# V2_2.net
KiCad netlist of a schematic drawn in EAGLE
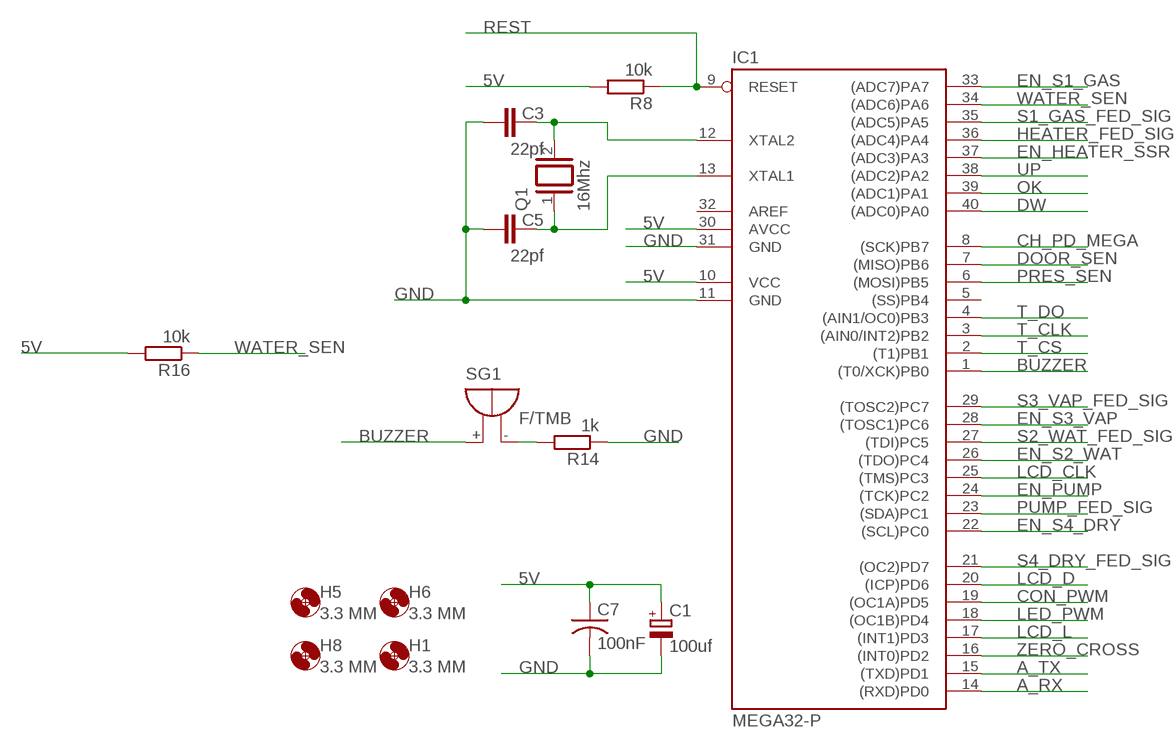
[diagram p0: schematic, sheet 1]
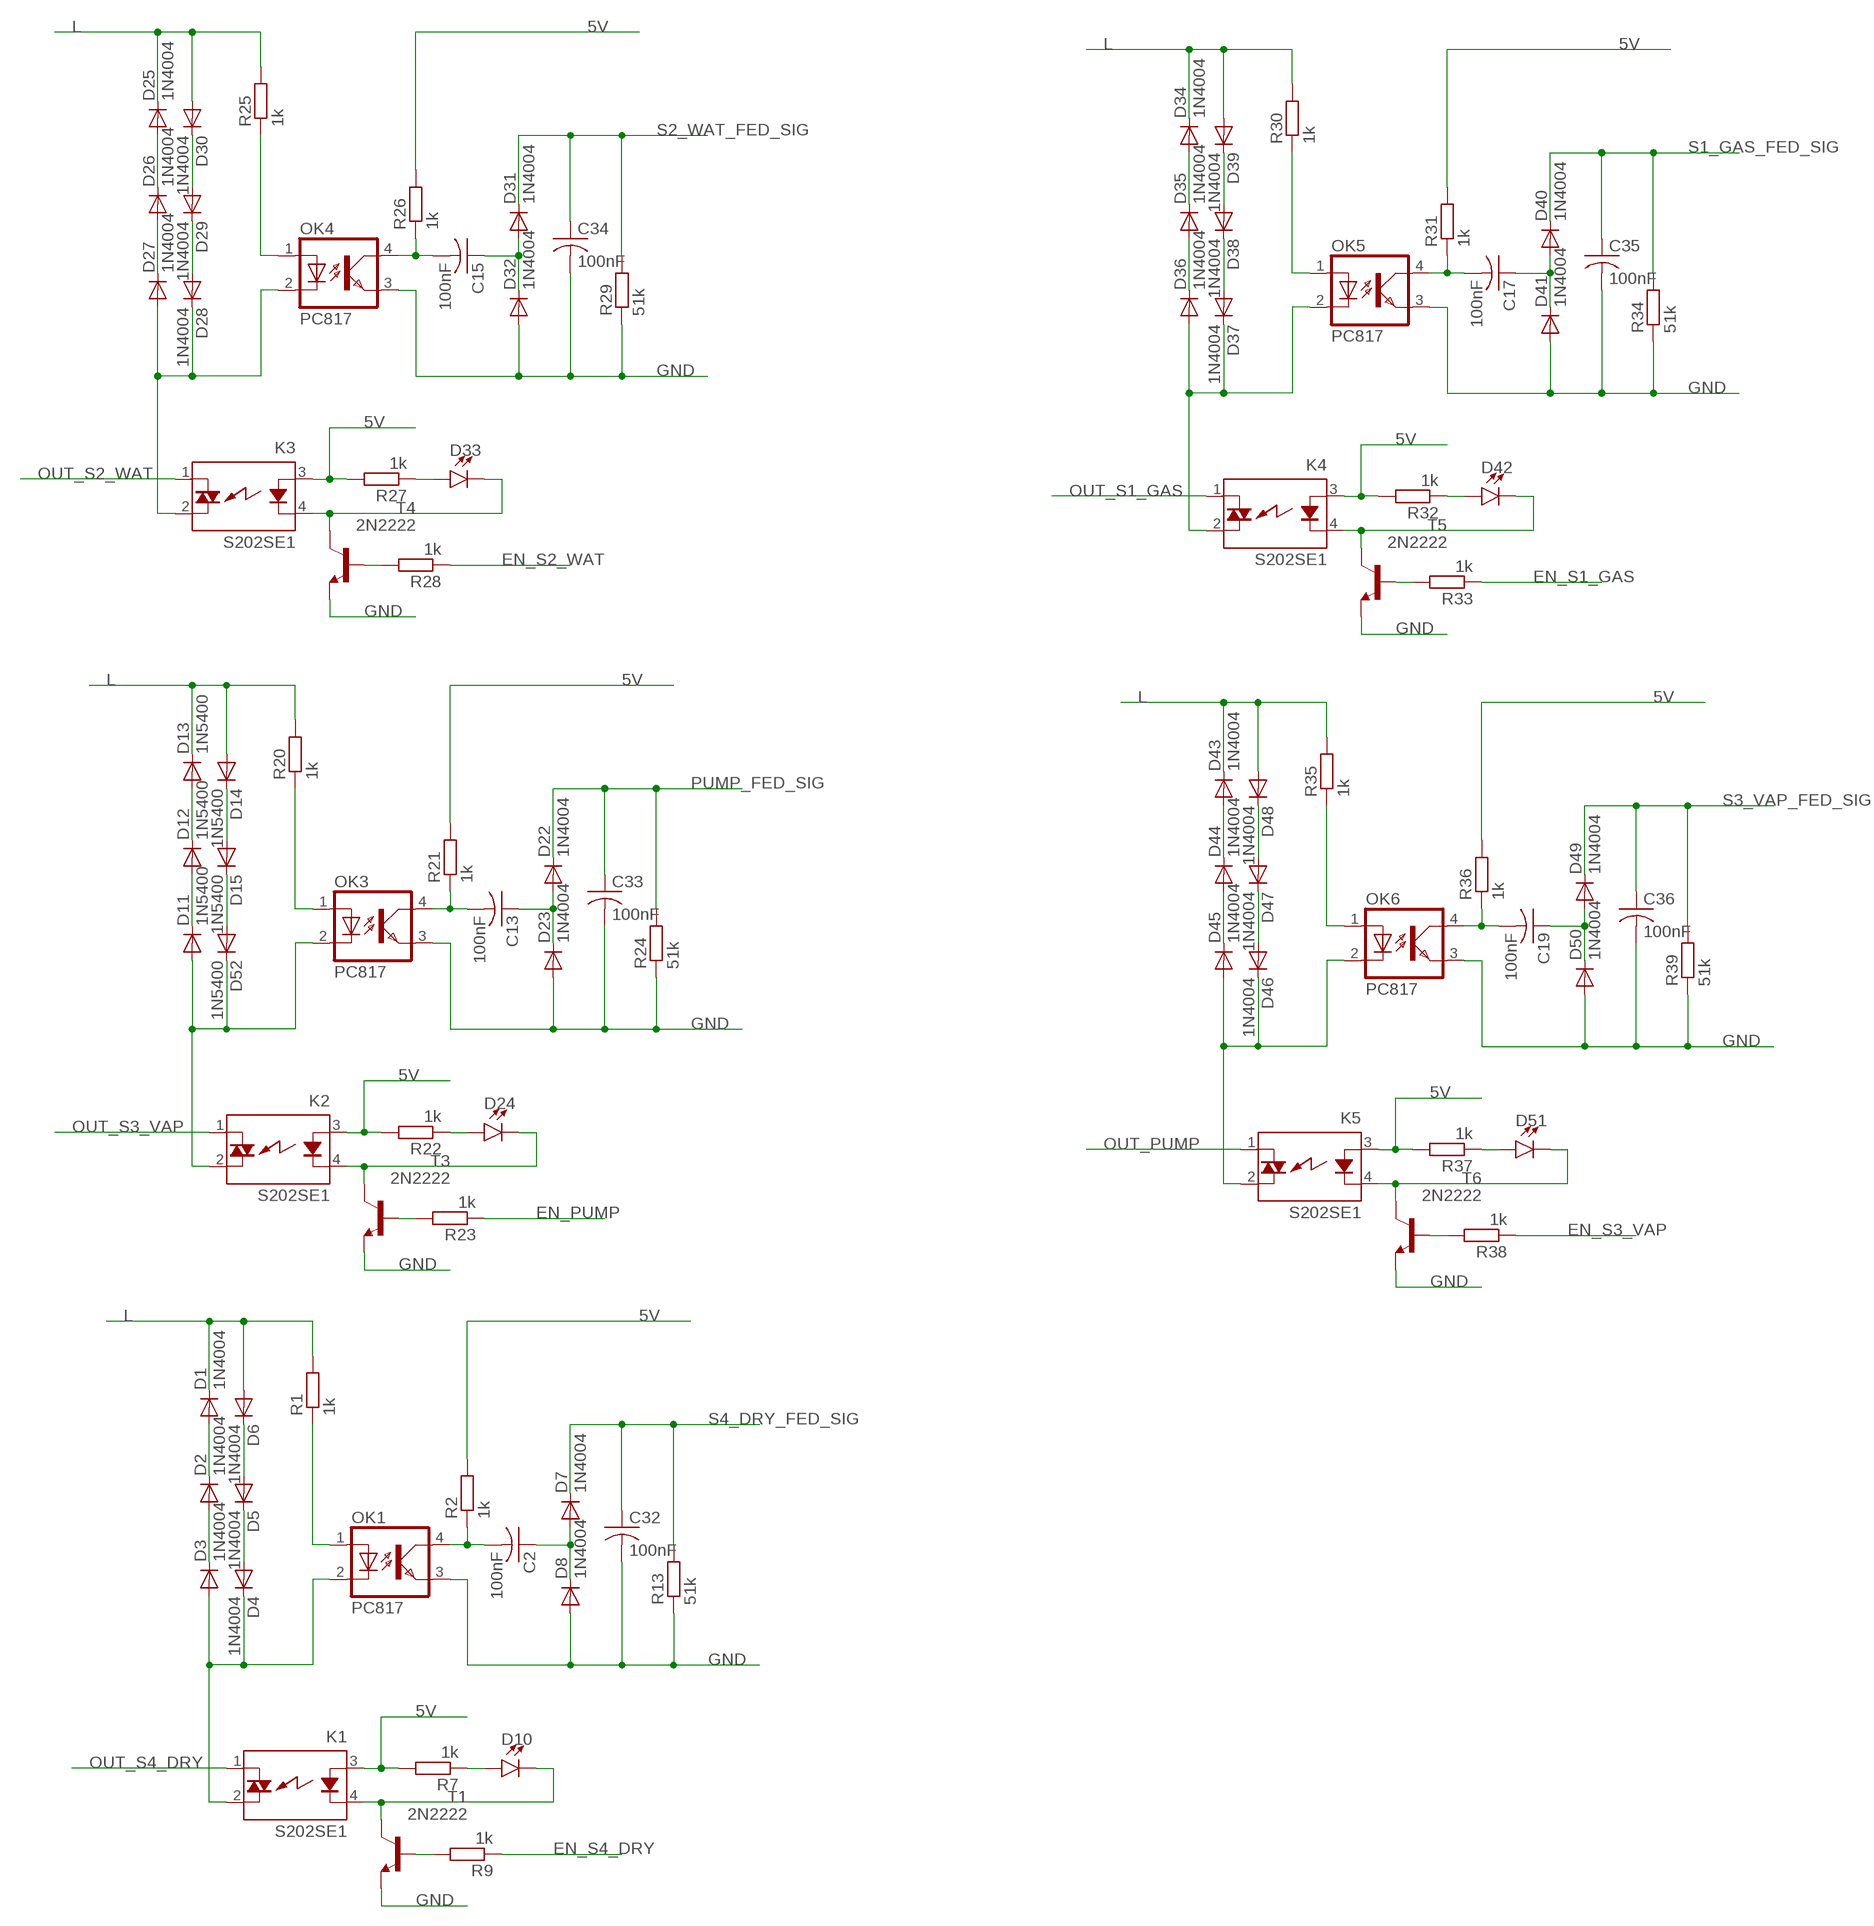
[diagram p1: schematic, sheet 2]
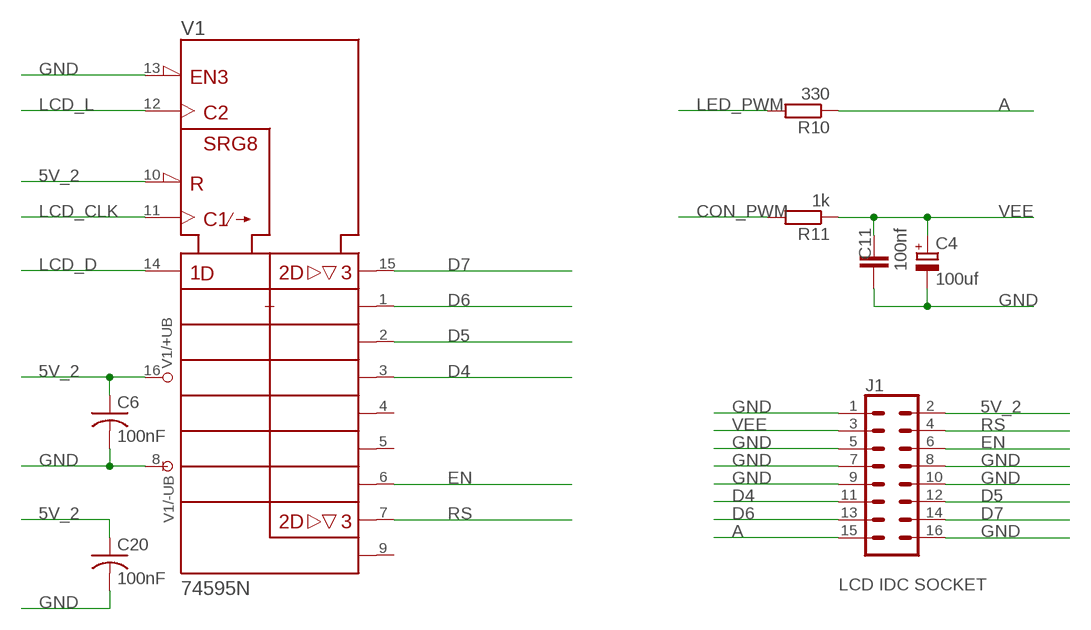
[diagram p2: schematic, sheet 3]
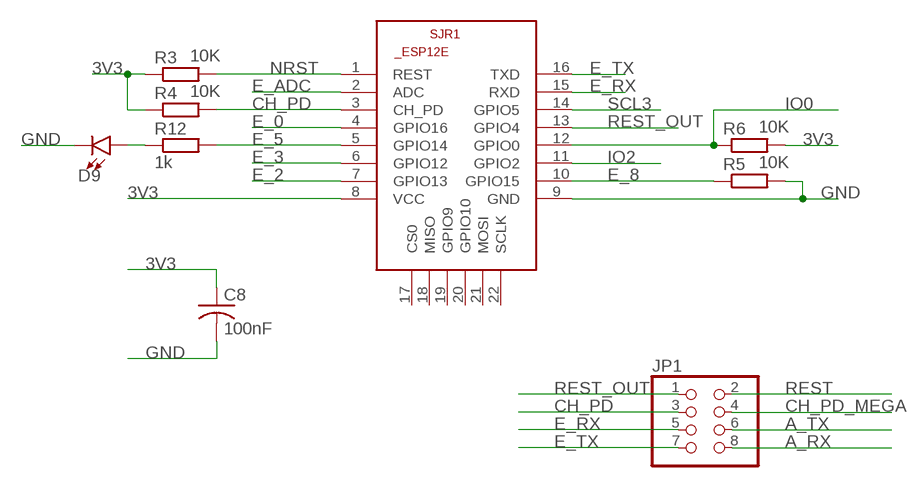
[diagram p3: schematic, sheet 4]
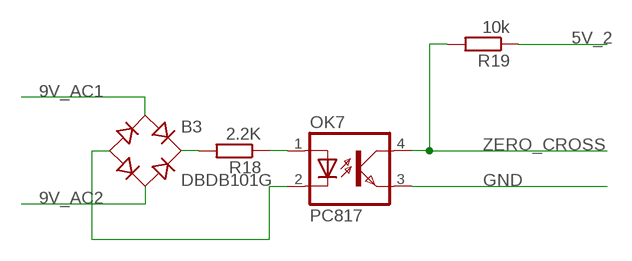
[diagram p4: schematic, sheet 5]
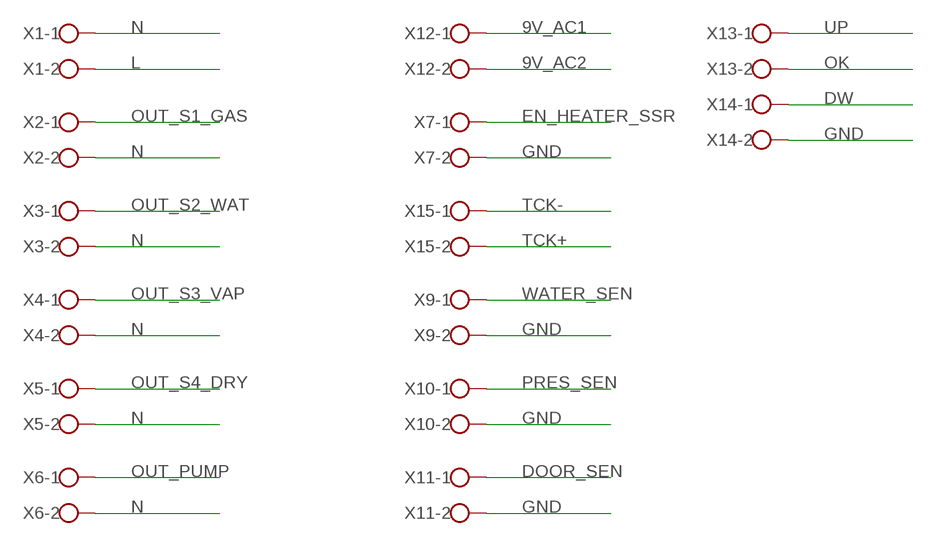
[diagram p5: schematic, sheet 6]
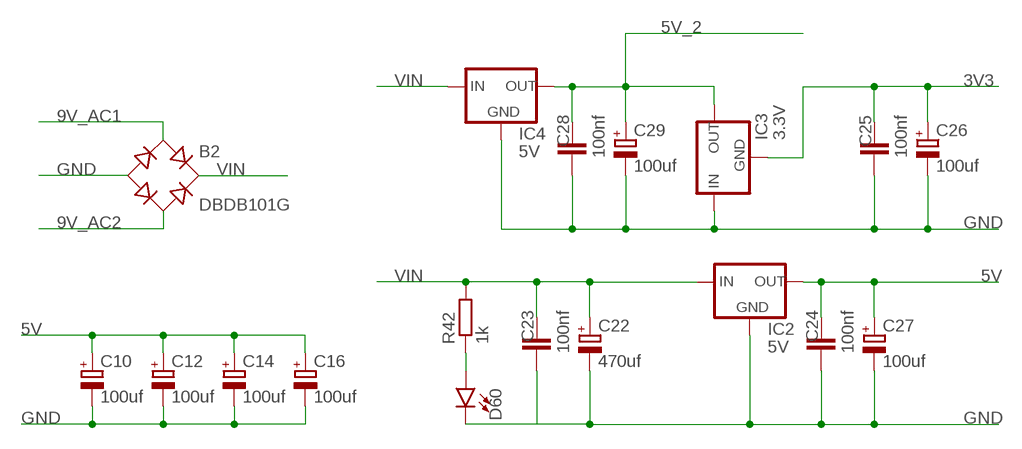
[diagram p6: schematic, sheet 7]
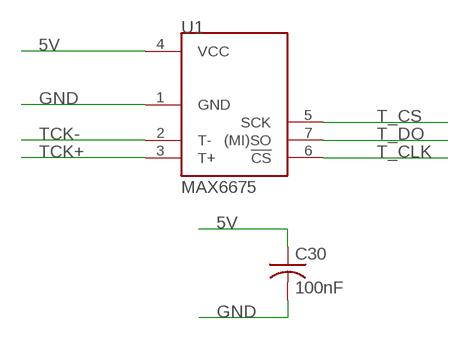
[diagram p7: schematic, sheet 8]

(export (version "E")
  (design (tool "Eeschema 10.0.6"))
  (components
    (comp (ref "C1")
      (value "100uf")
      (footprint "eagle-import:E3,5-8")
      (libsource (lib "eagle-import") (part "CPOL-EUE3.5-8"))
    )
    (comp (ref "C3")
      (value "22pf")
      (footprint "eagle-import:C050-030X075")
      (libsource (lib "eagle-import") (part "C-EU050-030X075"))
    )
    (comp (ref "C5")
      (value "22pf")
      (footprint "eagle-import:C050-030X075")
      (libsource (lib "eagle-import") (part "C-EU050-030X075"))
    )
    (comp (ref "C7")
      (value "100nF")
      (footprint "eagle-import:C050-035X075")
      (libsource (lib "eagle-import") (part "C-US050-035X075"))
    )
    (comp (ref "H1")
      (value "3.3 MM")
      (footprint "eagle-import:3,3")
      (libsource (lib "eagle-import") (part "MOUNT-HOLE3.3"))
    )
    (comp (ref "H5")
      (value "3.3 MM")
      (footprint "eagle-import:3,3")
      (libsource (lib "eagle-import") (part "MOUNT-HOLE3.3"))
    )
    (comp (ref "H6")
      (value "3.3 MM")
      (footprint "eagle-import:3,3")
      (libsource (lib "eagle-import") (part "MOUNT-HOLE3.3"))
    )
    (comp (ref "H8")
      (value "3.3 MM")
      (footprint "eagle-import:3,3")
      (libsource (lib "eagle-import") (part "MOUNT-HOLE3.3"))
    )
    (comp (ref "IC1")
      (value "MEGA32-P")
      (footprint "eagle-import:DIL40")
      (fields (field (name "MPN") "ATMEGA32-16PU"))
      (libsource (lib "eagle-import") (part "MEGA32-P"))
    )
    (comp (ref "Q1")
      (value "16Mhz")
      (footprint "eagle-import:QS")
      (libsource (lib "eagle-import") (part "XTAL/S"))
    )
    (comp (ref "R8")
      (value "10k")
      (footprint "eagle-import:0207_10")
      (libsource (lib "eagle-import") (part "R-EU_0207/10"))
    )
    (comp (ref "R14")
      (value "1k")
      (footprint "eagle-import:0207_10")
      (libsource (lib "eagle-import") (part "R-EU_0207/10"))
    )
    (comp (ref "R16")
      (value "10k")
      (footprint "eagle-import:0207_10")
      (libsource (lib "eagle-import") (part "R-EU_0207/10"))
    )
    (comp (ref "SG1")
      (value "F/TMB")
      (footprint "eagle-import:F_TMB")
      (libsource (lib "eagle-import") (part "F/TMB"))
    )
    (comp (ref "C8")
      (value "100nF")
      (footprint "eagle-import:C050-035X075")
      (libsource (lib "eagle-import") (part "C-US050-035X075"))
    )
    (comp (ref "D9")
      (value "LED5MM")
      (footprint "eagle-import:LED_5MM")
      (libsource (lib "eagle-import") (part "LED5MM"))
    )
    (comp (ref "JP1")
      (value "PINHD-2X4")
      (footprint "eagle-import:2X04")
      (libsource (lib "eagle-import") (part "PINHD-2X4"))
    )
    (comp (ref "R3")
      (value "10K")
      (footprint "eagle-import:0207_10")
      (libsource (lib "eagle-import") (part "rcl_334_R-EU_0207/10"))
    )
    (comp (ref "R4")
      (value "10K")
      (footprint "eagle-import:0207_10")
      (libsource (lib "eagle-import") (part "rcl_334_R-EU_0207/10"))
    )
    (comp (ref "R5")
      (value "10K")
      (footprint "eagle-import:0207_10")
      (libsource (lib "eagle-import") (part "rcl_334_R-EU_0207/10"))
    )
    (comp (ref "R6")
      (value "10K")
      (footprint "eagle-import:0207_10")
      (libsource (lib "eagle-import") (part "rcl_334_R-EU_0207/10"))
    )
    (comp (ref "R12")
      (value "1k")
      (footprint "eagle-import:0207_10")
      (libsource (lib "eagle-import") (part "R-EU_0207/10"))
    )
    (comp (ref "SJR1")
      (value "ESP8266-12EESP12E")
      (footprint "eagle-import:ESP8266-ESP12E")
      (libsource (lib "eagle-import") (part "ESP8266-12EESP12E"))
    )
    (comp (ref "B2")
      (value "DBDB101G")
      (footprint "eagle-import:DB")
      (libsource (lib "eagle-import") (part "DB?GDB101"))
    )
    (comp (ref "C10")
      (value "100uf")
      (footprint "eagle-import:E3,5-8")
      (libsource (lib "eagle-import") (part "CPOL-EUE3.5-8"))
    )
    (comp (ref "C12")
      (value "100uf")
      (footprint "eagle-import:E3,5-8")
      (libsource (lib "eagle-import") (part "CPOL-EUE3.5-8"))
    )
    (comp (ref "C14")
      (value "100uf")
      (footprint "eagle-import:E3,5-8")
      (libsource (lib "eagle-import") (part "CPOL-EUE3.5-8"))
    )
    (comp (ref "C16")
      (value "100uf")
      (footprint "eagle-import:E3,5-8")
      (libsource (lib "eagle-import") (part "CPOL-EUE3.5-8"))
    )
    (comp (ref "C22")
      (value "470uf")
      (footprint "eagle-import:E3,5-8")
      (libsource (lib "eagle-import") (part "CPOL-EUE3.5-8"))
    )
    (comp (ref "C23")
      (value "100nf")
      (footprint "eagle-import:C050-030X075")
      (libsource (lib "eagle-import") (part "C-EU050-030X075"))
    )
    (comp (ref "C24")
      (value "100nf")
      (footprint "eagle-import:C050-030X075")
      (libsource (lib "eagle-import") (part "C-EU050-030X075"))
    )
    (comp (ref "C25")
      (value "100nf")
      (footprint "eagle-import:C050-030X075")
      (libsource (lib "eagle-import") (part "C-EU050-030X075"))
    )
    (comp (ref "C26")
      (value "100uf")
      (footprint "eagle-import:E3,5-8")
      (libsource (lib "eagle-import") (part "CPOL-EUE3.5-8"))
    )
    (comp (ref "C27")
      (value "100uf")
      (footprint "eagle-import:E3,5-8")
      (libsource (lib "eagle-import") (part "CPOL-EUE3.5-8"))
    )
    (comp (ref "C28")
      (value "100nf")
      (footprint "eagle-import:C050-030X075")
      (libsource (lib "eagle-import") (part "C-EU050-030X075"))
    )
    (comp (ref "C29")
      (value "100uf")
      (footprint "eagle-import:E3,5-8")
      (libsource (lib "eagle-import") (part "CPOL-EUE3.5-8"))
    )
    (comp (ref "D60")
      (value "LED5MM")
      (footprint "eagle-import:LED_5MM")
      (libsource (lib "eagle-import") (part "LED5MM"))
    )
    (comp (ref "IC2")
      (value "5V")
      (footprint "eagle-import:78XXL")
      (libsource (lib "eagle-import") (part "V_REG_78XXSIDE"))
    )
    (comp (ref "IC3")
      (value "3.3V")
      (footprint "eagle-import:78XXL")
      (libsource (lib "eagle-import") (part "V_REG_78XXSIDE"))
    )
    (comp (ref "IC4")
      (value "5V")
      (footprint "eagle-import:78XXL")
      (libsource (lib "eagle-import") (part "V_REG_78XXSIDE"))
    )
    (comp (ref "R42")
      (value "1k")
      (footprint "eagle-import:0207_10")
      (libsource (lib "eagle-import") (part "R-EU_0207/10"))
    )
    (comp (ref "X1")
      (value "W237-102")
      (footprint "eagle-import:W237-102")
      (fields (field (name "MPN") "237-102"))
      (libsource (lib "eagle-import") (part "W237-102"))
    )
    (comp (ref "X2")
      (value "W237-102")
      (footprint "eagle-import:W237-102")
      (fields (field (name "MPN") "237-102"))
      (libsource (lib "eagle-import") (part "W237-102"))
    )
    (comp (ref "X3")
      (value "W237-102")
      (footprint "eagle-import:W237-102")
      (fields (field (name "MPN") "237-102"))
      (libsource (lib "eagle-import") (part "W237-102"))
    )
    (comp (ref "X4")
      (value "W237-102")
      (footprint "eagle-import:W237-102")
      (fields (field (name "MPN") "237-102"))
      (libsource (lib "eagle-import") (part "W237-102"))
    )
    (comp (ref "X5")
      (value "W237-102")
      (footprint "eagle-import:W237-102")
      (fields (field (name "MPN") "237-102"))
      (libsource (lib "eagle-import") (part "W237-102"))
    )
    (comp (ref "X6")
      (value "W237-102")
      (footprint "eagle-import:W237-102")
      (fields (field (name "MPN") "237-102"))
      (libsource (lib "eagle-import") (part "W237-102"))
    )
    (comp (ref "X7")
      (value "W237-102")
      (footprint "eagle-import:W237-102")
      (fields (field (name "MPN") "237-102"))
      (libsource (lib "eagle-import") (part "W237-102"))
    )
    (comp (ref "X9")
      (value "W237-102")
      (footprint "eagle-import:W237-102")
      (fields (field (name "MPN") "237-102"))
      (libsource (lib "eagle-import") (part "W237-102"))
    )
    (comp (ref "X10")
      (value "W237-102")
      (footprint "eagle-import:W237-102")
      (fields (field (name "MPN") "237-102"))
      (libsource (lib "eagle-import") (part "W237-102"))
    )
    (comp (ref "X11")
      (value "W237-102")
      (footprint "eagle-import:W237-102")
      (fields (field (name "MPN") "237-102"))
      (libsource (lib "eagle-import") (part "W237-102"))
    )
    (comp (ref "X12")
      (value "W237-102")
      (footprint "eagle-import:W237-102")
      (fields (field (name "MPN") "237-102"))
      (libsource (lib "eagle-import") (part "W237-102"))
    )
    (comp (ref "X13")
      (value "W237-102")
      (footprint "eagle-import:W237-102")
      (fields (field (name "MPN") "237-102"))
      (libsource (lib "eagle-import") (part "W237-102"))
    )
    (comp (ref "X14")
      (value "W237-102")
      (footprint "eagle-import:W237-102")
      (fields (field (name "MPN") "237-102"))
      (libsource (lib "eagle-import") (part "W237-102"))
    )
    (comp (ref "X15")
      (value "W237-102")
      (footprint "eagle-import:W237-102")
      (fields (field (name "MPN") "237-102"))
      (libsource (lib "eagle-import") (part "W237-102"))
    )
    (comp (ref "C2")
      (value "100nF")
      (footprint "eagle-import:C050-035X075")
      (libsource (lib "eagle-import") (part "C-US050-035X075"))
    )
    (comp (ref "C13")
      (value "100nF")
      (footprint "eagle-import:C050-035X075")
      (libsource (lib "eagle-import") (part "C-US050-035X075"))
    )
    (comp (ref "C15")
      (value "100nF")
      (footprint "eagle-import:C050-035X075")
      (libsource (lib "eagle-import") (part "C-US050-035X075"))
    )
    (comp (ref "C17")
      (value "100nF")
      (footprint "eagle-import:C050-035X075")
      (libsource (lib "eagle-import") (part "C-US050-035X075"))
    )
    (comp (ref "C19")
      (value "100nF")
      (footprint "eagle-import:C050-035X075")
      (libsource (lib "eagle-import") (part "C-US050-035X075"))
    )
    (comp (ref "C32")
      (value "100nF")
      (footprint "eagle-import:C050-035X075")
      (libsource (lib "eagle-import") (part "C-US050-035X075"))
    )
    (comp (ref "C33")
      (value "100nF")
      (footprint "eagle-import:C050-035X075")
      (libsource (lib "eagle-import") (part "C-US050-035X075"))
    )
    (comp (ref "C34")
      (value "100nF")
      (footprint "eagle-import:C050-035X075")
      (libsource (lib "eagle-import") (part "C-US050-035X075"))
    )
    (comp (ref "C35")
      (value "100nF")
      (footprint "eagle-import:C050-035X075")
      (libsource (lib "eagle-import") (part "C-US050-035X075"))
    )
    (comp (ref "C36")
      (value "100nF")
      (footprint "eagle-import:C050-035X075")
      (libsource (lib "eagle-import") (part "C-US050-035X075"))
    )
    (comp (ref "D1")
      (value "1N4004")
      (footprint "eagle-import:DO41-10")
      (libsource (lib "eagle-import") (part "1N4004"))
    )
    (comp (ref "D2")
      (value "1N4004")
      (footprint "eagle-import:DO41-10")
      (libsource (lib "eagle-import") (part "1N4004"))
    )
    (comp (ref "D3")
      (value "1N4004")
      (footprint "eagle-import:DO41-10")
      (libsource (lib "eagle-import") (part "1N4004"))
    )
    (comp (ref "D4")
      (value "1N4004")
      (footprint "eagle-import:DO41-10")
      (libsource (lib "eagle-import") (part "1N4004"))
    )
    (comp (ref "D5")
      (value "1N4004")
      (footprint "eagle-import:DO41-10")
      (libsource (lib "eagle-import") (part "1N4004"))
    )
    (comp (ref "D6")
      (value "1N4004")
      (footprint "eagle-import:DO41-10")
      (libsource (lib "eagle-import") (part "1N4004"))
    )
    (comp (ref "D7")
      (value "1N4004")
      (footprint "eagle-import:DO41-10")
      (libsource (lib "eagle-import") (part "1N4004"))
    )
    (comp (ref "D8")
      (value "1N4004")
      (footprint "eagle-import:DO41-10")
      (libsource (lib "eagle-import") (part "1N4004"))
    )
    (comp (ref "D10")
      (value "LED5MM")
      (footprint "eagle-import:LED_5MM")
      (libsource (lib "eagle-import") (part "LED5MM"))
    )
    (comp (ref "D11")
      (value "1N5400")
      (footprint "eagle-import:DO201-15")
      (libsource (lib "eagle-import") (part "1N5400"))
    )
    (comp (ref "D12")
      (value "1N5400")
      (footprint "eagle-import:DO201-15")
      (libsource (lib "eagle-import") (part "1N5400"))
    )
    (comp (ref "D13")
      (value "1N5400")
      (footprint "eagle-import:DO201-15")
      (libsource (lib "eagle-import") (part "1N5400"))
    )
    (comp (ref "D14")
      (value "1N5400")
      (footprint "eagle-import:DO201-15")
      (libsource (lib "eagle-import") (part "1N5400"))
    )
    (comp (ref "D15")
      (value "1N5400")
      (footprint "eagle-import:DO201-15")
      (libsource (lib "eagle-import") (part "1N5400"))
    )
    (comp (ref "D22")
      (value "1N4004")
      (footprint "eagle-import:DO41-10")
      (libsource (lib "eagle-import") (part "1N4004"))
    )
    (comp (ref "D23")
      (value "1N4004")
      (footprint "eagle-import:DO41-10")
      (libsource (lib "eagle-import") (part "1N4004"))
    )
    (comp (ref "D24")
      (value "LED5MM")
      (footprint "eagle-import:LED_5MM")
      (libsource (lib "eagle-import") (part "LED5MM"))
    )
    (comp (ref "D25")
      (value "1N4004")
      (footprint "eagle-import:DO41-10")
      (libsource (lib "eagle-import") (part "1N4004"))
    )
    (comp (ref "D26")
      (value "1N4004")
      (footprint "eagle-import:DO41-10")
      (libsource (lib "eagle-import") (part "1N4004"))
    )
    (comp (ref "D27")
      (value "1N4004")
      (footprint "eagle-import:DO41-10")
      (libsource (lib "eagle-import") (part "1N4004"))
    )
    (comp (ref "D28")
      (value "1N4004")
      (footprint "eagle-import:DO41-10")
      (libsource (lib "eagle-import") (part "1N4004"))
    )
    (comp (ref "D29")
      (value "1N4004")
      (footprint "eagle-import:DO41-10")
      (libsource (lib "eagle-import") (part "1N4004"))
    )
    (comp (ref "D30")
      (value "1N4004")
      (footprint "eagle-import:DO41-10")
      (libsource (lib "eagle-import") (part "1N4004"))
    )
    (comp (ref "D31")
      (value "1N4004")
      (footprint "eagle-import:DO41-10")
      (libsource (lib "eagle-import") (part "1N4004"))
    )
    (comp (ref "D32")
      (value "1N4004")
      (footprint "eagle-import:DO41-10")
      (libsource (lib "eagle-import") (part "1N4004"))
    )
    (comp (ref "D33")
      (value "LED5MM")
      (footprint "eagle-import:LED_5MM")
      (libsource (lib "eagle-import") (part "LED5MM"))
    )
    (comp (ref "D34")
      (value "1N4004")
      (footprint "eagle-import:DO41-10")
      (libsource (lib "eagle-import") (part "1N4004"))
    )
    (comp (ref "D35")
      (value "1N4004")
      (footprint "eagle-import:DO41-10")
      (libsource (lib "eagle-import") (part "1N4004"))
    )
    (comp (ref "D36")
      (value "1N4004")
      (footprint "eagle-import:DO41-10")
      (libsource (lib "eagle-import") (part "1N4004"))
    )
    (comp (ref "D37")
      (value "1N4004")
      (footprint "eagle-import:DO41-10")
      (libsource (lib "eagle-import") (part "1N4004"))
    )
    (comp (ref "D38")
      (value "1N4004")
      (footprint "eagle-import:DO41-10")
      (libsource (lib "eagle-import") (part "1N4004"))
    )
    (comp (ref "D39")
      (value "1N4004")
      (footprint "eagle-import:DO41-10")
      (libsource (lib "eagle-import") (part "1N4004"))
    )
    (comp (ref "D40")
      (value "1N4004")
      (footprint "eagle-import:DO41-10")
      (libsource (lib "eagle-import") (part "1N4004"))
    )
    (comp (ref "D41")
      (value "1N4004")
      (footprint "eagle-import:DO41-10")
      (libsource (lib "eagle-import") (part "1N4004"))
    )
    (comp (ref "D42")
      (value "LED5MM")
      (footprint "eagle-import:LED_5MM")
      (libsource (lib "eagle-import") (part "LED5MM"))
    )
    (comp (ref "D43")
      (value "1N4004")
      (footprint "eagle-import:DO41-10")
      (libsource (lib "eagle-import") (part "1N4004"))
    )
    (comp (ref "D44")
      (value "1N4004")
      (footprint "eagle-import:DO41-10")
      (libsource (lib "eagle-import") (part "1N4004"))
    )
    (comp (ref "D45")
      (value "1N4004")
      (footprint "eagle-import:DO41-10")
      (libsource (lib "eagle-import") (part "1N4004"))
    )
    (comp (ref "D46")
      (value "1N4004")
      (footprint "eagle-import:DO41-10")
      (libsource (lib "eagle-import") (part "1N4004"))
    )
    (comp (ref "D47")
      (value "1N4004")
      (footprint "eagle-import:DO41-10")
      (libsource (lib "eagle-import") (part "1N4004"))
    )
    (comp (ref "D48")
      (value "1N4004")
      (footprint "eagle-import:DO41-10")
      (libsource (lib "eagle-import") (part "1N4004"))
    )
    (comp (ref "D49")
      (value "1N4004")
      (footprint "eagle-import:DO41-10")
      (libsource (lib "eagle-import") (part "1N4004"))
    )
    (comp (ref "D50")
      (value "1N4004")
      (footprint "eagle-import:DO41-10")
      (libsource (lib "eagle-import") (part "1N4004"))
    )
    (comp (ref "D51")
      (value "LED5MM")
      (footprint "eagle-import:LED_5MM")
      (libsource (lib "eagle-import") (part "LED5MM"))
    )
    (comp (ref "D52")
      (value "1N5400")
      (footprint "eagle-import:DO201-15")
      (libsource (lib "eagle-import") (part "1N5400"))
    )
    (comp (ref "K1")
      (value "S202SE1")
      (footprint "eagle-import:S2XXEX")
      (libsource (lib "eagle-import") (part "S202SE1"))
    )
    (comp (ref "K2")
      (value "S202SE1")
      (footprint "eagle-import:S2XXEX")
      (libsource (lib "eagle-import") (part "S202SE1"))
    )
    (comp (ref "K3")
      (value "S202SE1")
      (footprint "eagle-import:S2XXEX")
      (libsource (lib "eagle-import") (part "S202SE1"))
    )
    (comp (ref "K4")
      (value "S202SE1")
      (footprint "eagle-import:S2XXEX")
      (libsource (lib "eagle-import") (part "S202SE1"))
    )
    (comp (ref "K5")
      (value "S202SE1")
      (footprint "eagle-import:S2XXEX")
      (libsource (lib "eagle-import") (part "S202SE1"))
    )
    (comp (ref "OK1")
      (value "PC817")
      (footprint "eagle-import:DIL04")
      (libsource (lib "eagle-import") (part "PC817"))
    )
    (comp (ref "OK3")
      (value "PC817")
      (footprint "eagle-import:DIL04")
      (libsource (lib "eagle-import") (part "PC817"))
    )
    (comp (ref "OK4")
      (value "PC817")
      (footprint "eagle-import:DIL04")
      (libsource (lib "eagle-import") (part "PC817"))
    )
    (comp (ref "OK5")
      (value "PC817")
      (footprint "eagle-import:DIL04")
      (libsource (lib "eagle-import") (part "PC817"))
    )
    (comp (ref "OK6")
      (value "PC817")
      (footprint "eagle-import:DIL04")
      (libsource (lib "eagle-import") (part "PC817"))
    )
    (comp (ref "R1")
      (value "1k")
      (footprint "eagle-import:0207_10")
      (libsource (lib "eagle-import") (part "R-EU_0207/10"))
    )
    (comp (ref "R2")
      (value "1k")
      (footprint "eagle-import:0207_10")
      (libsource (lib "eagle-import") (part "R-EU_0207/10"))
    )
    (comp (ref "R7")
      (value "1k")
      (footprint "eagle-import:0207_10")
      (libsource (lib "eagle-import") (part "R-EU_0207/10"))
    )
    (comp (ref "R9")
      (value "1k")
      (footprint "eagle-import:0207_10")
      (libsource (lib "eagle-import") (part "R-EU_0207/10"))
    )
    (comp (ref "R13")
      (value "51k")
      (footprint "eagle-import:0207_10")
      (libsource (lib "eagle-import") (part "R-EU_0207/10"))
    )
    (comp (ref "R20")
      (value "1k")
      (footprint "eagle-import:0207_10")
      (libsource (lib "eagle-import") (part "R-EU_0207/10"))
    )
    (comp (ref "R21")
      (value "1k")
      (footprint "eagle-import:0207_10")
      (libsource (lib "eagle-import") (part "R-EU_0207/10"))
    )
    (comp (ref "R22")
      (value "1k")
      (footprint "eagle-import:0207_10")
      (libsource (lib "eagle-import") (part "R-EU_0207/10"))
    )
    (comp (ref "R23")
      (value "1k")
      (footprint "eagle-import:0207_10")
      (libsource (lib "eagle-import") (part "R-EU_0207/10"))
    )
    (comp (ref "R24")
      (value "51k")
      (footprint "eagle-import:0207_10")
      (libsource (lib "eagle-import") (part "R-EU_0207/10"))
    )
    (comp (ref "R25")
      (value "1k")
      (footprint "eagle-import:0207_10")
      (libsource (lib "eagle-import") (part "R-EU_0207/10"))
    )
    (comp (ref "R26")
      (value "1k")
      (footprint "eagle-import:0207_10")
      (libsource (lib "eagle-import") (part "R-EU_0207/10"))
    )
    (comp (ref "R27")
      (value "1k")
      (footprint "eagle-import:0207_10")
      (libsource (lib "eagle-import") (part "R-EU_0207/10"))
    )
    (comp (ref "R28")
      (value "1k")
      (footprint "eagle-import:0207_10")
      (libsource (lib "eagle-import") (part "R-EU_0207/10"))
    )
    (comp (ref "R29")
      (value "51k")
      (footprint "eagle-import:0207_10")
      (libsource (lib "eagle-import") (part "R-EU_0207/10"))
    )
    (comp (ref "R30")
      (value "1k")
      (footprint "eagle-import:0207_10")
      (libsource (lib "eagle-import") (part "R-EU_0207/10"))
    )
    (comp (ref "R31")
      (value "1k")
      (footprint "eagle-import:0207_10")
      (libsource (lib "eagle-import") (part "R-EU_0207/10"))
    )
    (comp (ref "R32")
      (value "1k")
      (footprint "eagle-import:0207_10")
      (libsource (lib "eagle-import") (part "R-EU_0207/10"))
    )
    (comp (ref "R33")
      (value "1k")
      (footprint "eagle-import:0207_10")
      (libsource (lib "eagle-import") (part "R-EU_0207/10"))
    )
    (comp (ref "R34")
      (value "51k")
      (footprint "eagle-import:0207_10")
      (libsource (lib "eagle-import") (part "R-EU_0207/10"))
    )
    (comp (ref "R35")
      (value "1k")
      (footprint "eagle-import:0207_10")
      (libsource (lib "eagle-import") (part "R-EU_0207/10"))
    )
    (comp (ref "R36")
      (value "1k")
      (footprint "eagle-import:0207_10")
      (libsource (lib "eagle-import") (part "R-EU_0207/10"))
    )
    (comp (ref "R37")
      (value "1k")
      (footprint "eagle-import:0207_10")
      (libsource (lib "eagle-import") (part "R-EU_0207/10"))
    )
    (comp (ref "R38")
      (value "1k")
      (footprint "eagle-import:0207_10")
      (libsource (lib "eagle-import") (part "R-EU_0207/10"))
    )
    (comp (ref "R39")
      (value "51k")
      (footprint "eagle-import:0207_10")
      (libsource (lib "eagle-import") (part "R-EU_0207/10"))
    )
    (comp (ref "T1")
      (value "2N2222")
      (footprint "eagle-import:TO92-EBC-OVAL")
      (libsource (lib "eagle-import") (part "2N2222"))
    )
    (comp (ref "T3")
      (value "2N2222")
      (footprint "eagle-import:TO92-EBC-OVAL")
      (libsource (lib "eagle-import") (part "2N2222"))
    )
    (comp (ref "T4")
      (value "2N2222")
      (footprint "eagle-import:TO92-EBC-OVAL")
      (libsource (lib "eagle-import") (part "2N2222"))
    )
    (comp (ref "T5")
      (value "2N2222")
      (footprint "eagle-import:TO92-EBC-OVAL")
      (libsource (lib "eagle-import") (part "2N2222"))
    )
    (comp (ref "T6")
      (value "2N2222")
      (footprint "eagle-import:TO92-EBC-OVAL")
      (libsource (lib "eagle-import") (part "2N2222"))
    )
    (comp (ref "C4")
      (value "100uf")
      (footprint "eagle-import:E3,5-8")
      (libsource (lib "eagle-import") (part "CPOL-EUE3.5-8"))
    )
    (comp (ref "C6")
      (value "100nF")
      (footprint "eagle-import:C050-035X075")
      (libsource (lib "eagle-import") (part "C-US050-035X075"))
    )
    (comp (ref "C11")
      (value "100nf")
      (footprint "eagle-import:C050-030X075")
      (libsource (lib "eagle-import") (part "C-EU050-030X075"))
    )
    (comp (ref "C20")
      (value "100nF")
      (footprint "eagle-import:C050-035X075")
      (libsource (lib "eagle-import") (part "C-US050-035X075"))
    )
    (comp (ref "J1")
      (value "CONN_08X2")
      (footprint "eagle-import:2X8")
      (libsource (lib "eagle-import") (part "CONN_08X2"))
    )
    (comp (ref "R10")
      (value "330")
      (footprint "eagle-import:0207_10")
      (libsource (lib "eagle-import") (part "R-EU_0207/10"))
    )
    (comp (ref "R11")
      (value "1k")
      (footprint "eagle-import:0207_10")
      (libsource (lib "eagle-import") (part "R-EU_0207/10"))
    )
    (comp (ref "V1")
      (value "74595N")
      (footprint "eagle-import:DIL16")
      (libsource (lib "eagle-import") (part "74595N"))
    )
    (comp (ref "B3")
      (value "DBDB101G")
      (footprint "eagle-import:DB")
      (libsource (lib "eagle-import") (part "DB?GDB101"))
    )
    (comp (ref "OK7")
      (value "PC817")
      (footprint "eagle-import:DIL04")
      (libsource (lib "eagle-import") (part "PC817"))
    )
    (comp (ref "R18")
      (value "2.2K")
      (footprint "eagle-import:0207_10")
      (libsource (lib "eagle-import") (part "R-EU_0207/10"))
    )
    (comp (ref "R19")
      (value "10k")
      (footprint "eagle-import:0207_10")
      (libsource (lib "eagle-import") (part "R-EU_0207/10"))
    )
    (comp (ref "C30")
      (value "100nF")
      (footprint "eagle-import:C050-035X075")
      (libsource (lib "eagle-import") (part "C-US050-035X075"))
    )
    (comp (ref "U1")
      (value "MAX6675")
      (footprint "eagle-import:SOIC8")
      (libsource (lib "eagle-import") (part "MAX6675"))
    )
  )
  (nets
    (net (code "1") (name "3V3") (class "Default")
      (node (ref "C25") (pin "2") (pinfunction "2_2") (pintype "passive"))
      (node (ref "C26") (pin "+") (pinfunction "+_+") (pintype "passive"))
      (node (ref "C8") (pin "1") (pinfunction "1_1") (pintype "passive"))
      (node (ref "IC3") (pin "GND") (pinfunction "GND_GND") (pintype "input"))
      (node (ref "R3") (pin "1") (pinfunction "1_1") (pintype "passive"))
      (node (ref "R4") (pin "1") (pinfunction "1_1") (pintype "passive"))
      (node (ref "R6") (pin "2") (pinfunction "2_2") (pintype "passive"))
      (node (ref "SJR1") (pin "8") (pinfunction "VCC_8") (pintype "bidirectional"))
    )
    (net (code "2") (name "5V") (class "Default")
      (node (ref "C1") (pin "+") (pinfunction "+_+") (pintype "passive"))
      (node (ref "C10") (pin "+") (pinfunction "+_+") (pintype "passive"))
      (node (ref "C12") (pin "+") (pinfunction "+_+") (pintype "passive"))
      (node (ref "C14") (pin "+") (pinfunction "+_+") (pintype "passive"))
      (node (ref "C16") (pin "+") (pinfunction "+_+") (pintype "passive"))
      (node (ref "C24") (pin "2") (pinfunction "2_2") (pintype "passive"))
      (node (ref "C27") (pin "+") (pinfunction "+_+") (pintype "passive"))
      (node (ref "C30") (pin "1") (pinfunction "1_1") (pintype "passive"))
      (node (ref "C7") (pin "1") (pinfunction "1_1") (pintype "passive"))
      (node (ref "IC1") (pin "10") (pinfunction "VCC_10") (pintype "power_in"))
      (node (ref "IC1") (pin "30") (pinfunction "AVCC_30") (pintype "power_in"))
      (node (ref "IC2") (pin "OUT") (pinfunction "OUT_OUT") (pintype "output"))
      (node (ref "K1") (pin "3") (pinfunction "A_3") (pintype "passive"))
      (node (ref "K2") (pin "3") (pinfunction "A_3") (pintype "passive"))
      (node (ref "K3") (pin "3") (pinfunction "A_3") (pintype "passive"))
      (node (ref "K4") (pin "3") (pinfunction "A_3") (pintype "passive"))
      (node (ref "K5") (pin "3") (pinfunction "A_3") (pintype "passive"))
      (node (ref "R16") (pin "2") (pinfunction "2_2") (pintype "passive"))
      (node (ref "R2") (pin "2") (pinfunction "2_2") (pintype "passive"))
      (node (ref "R21") (pin "2") (pinfunction "2_2") (pintype "passive"))
      (node (ref "R22") (pin "2") (pinfunction "2_2") (pintype "passive"))
      (node (ref "R26") (pin "2") (pinfunction "2_2") (pintype "passive"))
      (node (ref "R27") (pin "2") (pinfunction "2_2") (pintype "passive"))
      (node (ref "R31") (pin "2") (pinfunction "2_2") (pintype "passive"))
      (node (ref "R32") (pin "2") (pinfunction "2_2") (pintype "passive"))
      (node (ref "R36") (pin "2") (pinfunction "2_2") (pintype "passive"))
      (node (ref "R37") (pin "2") (pinfunction "2_2") (pintype "passive"))
      (node (ref "R7") (pin "2") (pinfunction "2_2") (pintype "passive"))
      (node (ref "R8") (pin "2") (pinfunction "2_2") (pintype "passive"))
      (node (ref "U1") (pin "4") (pinfunction "VCC_4") (pintype "bidirectional"))
    )
    (net (code "3") (name "5V_2") (class "Default")
      (node (ref "C20") (pin "1") (pinfunction "1_1") (pintype "passive"))
      (node (ref "C28") (pin "2") (pinfunction "2_2") (pintype "passive"))
      (node (ref "C29") (pin "+") (pinfunction "+_+") (pintype "passive"))
      (node (ref "C6") (pin "1") (pinfunction "1_1") (pintype "passive"))
      (node (ref "IC3") (pin "OUT") (pinfunction "OUT_OUT") (pintype "output"))
      (node (ref "IC4") (pin "OUT") (pinfunction "OUT_OUT") (pintype "output"))
      (node (ref "J1") (pin "2") (pinfunction "2_2") (pintype "passive"))
      (node (ref "R19") (pin "1") (pinfunction "1_1") (pintype "passive"))
      (node (ref "V1") (pin "10") (pinfunction "~{SRCLR}_10") (pintype "input"))
      (node (ref "V1") (pin "16") (pinfunction "+UB_16") (pintype "power_in"))
    )
    (net (code "4") (name "9V_AC1") (class "Default")
      (node (ref "B2") (pin "AC1") (pinfunction "AC1_AC1") (pintype "passive"))
      (node (ref "B3") (pin "AC1") (pinfunction "AC1_AC1") (pintype "passive"))
      (node (ref "X12") (pin "1") (pinfunction "KL_1") (pintype "passive"))
    )
    (net (code "5") (name "9V_AC2") (class "Default")
      (node (ref "B2") (pin "AC2") (pinfunction "AC2_AC2") (pintype "passive"))
      (node (ref "B3") (pin "AC2") (pinfunction "AC2_AC2") (pintype "passive"))
      (node (ref "X12") (pin "2") (pinfunction "KL_2") (pintype "passive"))
    )
    (net (code "6") (name "A") (class "Default")
      (node (ref "J1") (pin "15") (pinfunction "15_15") (pintype "passive"))
      (node (ref "R10") (pin "1") (pinfunction "1_1") (pintype "passive"))
    )
    (net (code "7") (name "A_RX") (class "Default")
      (node (ref "IC1") (pin "14") (pinfunction "(RXD)PD0_14") (pintype "bidirectional"))
      (node (ref "JP1") (pin "8") (pinfunction "8_8") (pintype "passive"))
    )
    (net (code "8") (name "A_TX") (class "Default")
      (node (ref "IC1") (pin "15") (pinfunction "(TXD)PD1_15") (pintype "bidirectional"))
      (node (ref "JP1") (pin "6") (pinfunction "6_6") (pintype "passive"))
    )
    (net (code "9") (name "BUZZER") (class "Default")
      (node (ref "IC1") (pin "1") (pinfunction "(T0/XCK)PB0_1") (pintype "bidirectional"))
      (node (ref "SG1") (pin "+") (pinfunction "+_+") (pintype "passive"))
    )
    (net (code "10") (name "CH_PD") (class "Default")
      (node (ref "JP1") (pin "3") (pinfunction "3_3") (pintype "passive"))
      (node (ref "R4") (pin "2") (pinfunction "2_2") (pintype "passive"))
      (node (ref "SJR1") (pin "3") (pinfunction "CH_PD_3") (pintype "bidirectional"))
    )
    (net (code "11") (name "CH_PD_MEGA") (class "Default")
      (node (ref "IC1") (pin "8") (pinfunction "(SCK)PB7_8") (pintype "bidirectional"))
      (node (ref "JP1") (pin "4") (pinfunction "4_4") (pintype "passive"))
    )
    (net (code "12") (name "CON_PWM") (class "Default")
      (node (ref "IC1") (pin "19") (pinfunction "(OC1A)PD5_19") (pintype "bidirectional"))
      (node (ref "R11") (pin "2") (pinfunction "2_2") (pintype "passive"))
    )
    (net (code "13") (name "D4") (class "Default")
      (node (ref "J1") (pin "11") (pinfunction "11_11") (pintype "passive"))
      (node (ref "V1") (pin "3") (pinfunction "QD_3") (pintype "tri_state"))
    )
    (net (code "14") (name "D5") (class "Default")
      (node (ref "J1") (pin "12") (pinfunction "12_12") (pintype "passive"))
      (node (ref "V1") (pin "2") (pinfunction "QC_2") (pintype "tri_state"))
    )
    (net (code "15") (name "D6") (class "Default")
      (node (ref "J1") (pin "13") (pinfunction "13_13") (pintype "passive"))
      (node (ref "V1") (pin "1") (pinfunction "QB_1") (pintype "tri_state"))
    )
    (net (code "16") (name "D7") (class "Default")
      (node (ref "J1") (pin "14") (pinfunction "14_14") (pintype "passive"))
      (node (ref "V1") (pin "15") (pinfunction "QA_15") (pintype "tri_state"))
    )
    (net (code "17") (name "DOOR_SEN") (class "Default")
      (node (ref "IC1") (pin "7") (pinfunction "(MISO)PB6_7") (pintype "bidirectional"))
      (node (ref "X11") (pin "1") (pinfunction "KL_1") (pintype "passive"))
    )
    (net (code "18") (name "DW") (class "Default")
      (node (ref "IC1") (pin "40") (pinfunction "(ADC0)PA0_40") (pintype "bidirectional"))
      (node (ref "X14") (pin "1") (pinfunction "KL_1") (pintype "passive"))
    )
    (net (code "19") (name "EN") (class "Default")
      (node (ref "J1") (pin "6") (pinfunction "6_6") (pintype "passive"))
      (node (ref "V1") (pin "6") (pinfunction "QG_6") (pintype "tri_state"))
    )
    (net (code "20") (name "EN_HEATER_SSR") (class "Default")
      (node (ref "IC1") (pin "37") (pinfunction "(ADC3)PA3_37") (pintype "bidirectional"))
      (node (ref "X7") (pin "1") (pinfunction "KL_1") (pintype "passive"))
    )
    (net (code "21") (name "EN_PUMP") (class "Default")
      (node (ref "IC1") (pin "24") (pinfunction "(TCK)PC2_24") (pintype "bidirectional"))
      (node (ref "R23") (pin "1") (pinfunction "1_1") (pintype "passive"))
    )
    (net (code "22") (name "EN_S1_GAS") (class "Default")
      (node (ref "IC1") (pin "33") (pinfunction "(ADC7)PA7_33") (pintype "bidirectional"))
      (node (ref "R33") (pin "1") (pinfunction "1_1") (pintype "passive"))
    )
    (net (code "23") (name "EN_S2_WAT") (class "Default")
      (node (ref "IC1") (pin "26") (pinfunction "(TDO)PC4_26") (pintype "bidirectional"))
      (node (ref "R28") (pin "1") (pinfunction "1_1") (pintype "passive"))
    )
    (net (code "24") (name "EN_S3_VAP") (class "Default")
      (node (ref "IC1") (pin "28") (pinfunction "(TOSC1)PC6_28") (pintype "bidirectional"))
      (node (ref "R38") (pin "1") (pinfunction "1_1") (pintype "passive"))
    )
    (net (code "25") (name "EN_S4_DRY") (class "Default")
      (node (ref "IC1") (pin "22") (pinfunction "(SCL)PC0_22") (pintype "bidirectional"))
      (node (ref "R9") (pin "1") (pinfunction "1_1") (pintype "passive"))
    )
    (net (code "26") (name "E_0") (class "Default")
      (node (ref "SJR1") (pin "4") (pinfunction "GPIO16_4") (pintype "bidirectional"))
    )
    (net (code "27") (name "E_2") (class "Default")
      (node (ref "SJR1") (pin "7") (pinfunction "GPIO13_7") (pintype "bidirectional"))
    )
    (net (code "28") (name "E_3") (class "Default")
      (node (ref "SJR1") (pin "6") (pinfunction "GPIO12_6") (pintype "bidirectional"))
    )
    (net (code "29") (name "E_5") (class "Default")
      (node (ref "R12") (pin "2") (pinfunction "2_2") (pintype "passive"))
      (node (ref "SJR1") (pin "5") (pinfunction "GPIO14_5") (pintype "bidirectional"))
    )
    (net (code "30") (name "E_8") (class "Default")
      (node (ref "R5") (pin "1") (pinfunction "1_1") (pintype "passive"))
      (node (ref "SJR1") (pin "10") (pinfunction "GPIO15_10") (pintype "bidirectional"))
    )
    (net (code "31") (name "E_ADC") (class "Default")
      (node (ref "SJR1") (pin "2") (pinfunction "ADC_2") (pintype "bidirectional"))
    )
    (net (code "32") (name "E_RX") (class "Default")
      (node (ref "JP1") (pin "5") (pinfunction "5_5") (pintype "passive"))
      (node (ref "SJR1") (pin "15") (pinfunction "RXD_15") (pintype "bidirectional"))
    )
    (net (code "33") (name "E_TX") (class "Default")
      (node (ref "JP1") (pin "7") (pinfunction "7_7") (pintype "passive"))
      (node (ref "SJR1") (pin "16") (pinfunction "TXD_16") (pintype "bidirectional"))
    )
    (net (code "34") (name "GND") (class "Default")
      (node (ref "B2") (pin "-") (pinfunction "-_-") (pintype "passive"))
      (node (ref "C1") (pin "-") (pinfunction "-_-") (pintype "passive"))
      (node (ref "C10") (pin "-") (pinfunction "-_-") (pintype "passive"))
      (node (ref "C11") (pin "1") (pinfunction "1_1") (pintype "passive"))
      (node (ref "C12") (pin "-") (pinfunction "-_-") (pintype "passive"))
      (node (ref "C14") (pin "-") (pinfunction "-_-") (pintype "passive"))
      (node (ref "C16") (pin "-") (pinfunction "-_-") (pintype "passive"))
      (node (ref "C20") (pin "2") (pinfunction "2_2") (pintype "passive"))
      (node (ref "C22") (pin "-") (pinfunction "-_-") (pintype "passive"))
      (node (ref "C23") (pin "1") (pinfunction "1_1") (pintype "passive"))
      (node (ref "C24") (pin "1") (pinfunction "1_1") (pintype "passive"))
      (node (ref "C25") (pin "1") (pinfunction "1_1") (pintype "passive"))
      (node (ref "C26") (pin "-") (pinfunction "-_-") (pintype "passive"))
      (node (ref "C27") (pin "-") (pinfunction "-_-") (pintype "passive"))
      (node (ref "C28") (pin "1") (pinfunction "1_1") (pintype "passive"))
      (node (ref "C29") (pin "-") (pinfunction "-_-") (pintype "passive"))
      (node (ref "C3") (pin "1") (pinfunction "1_1") (pintype "passive"))
      (node (ref "C30") (pin "2") (pinfunction "2_2") (pintype "passive"))
      (node (ref "C32") (pin "2") (pinfunction "2_2") (pintype "passive"))
      (node (ref "C33") (pin "2") (pinfunction "2_2") (pintype "passive"))
      (node (ref "C34") (pin "2") (pinfunction "2_2") (pintype "passive"))
      (node (ref "C35") (pin "2") (pinfunction "2_2") (pintype "passive"))
      (node (ref "C36") (pin "2") (pinfunction "2_2") (pintype "passive"))
      (node (ref "C4") (pin "-") (pinfunction "-_-") (pintype "passive"))
      (node (ref "C5") (pin "1") (pinfunction "1_1") (pintype "passive"))
      (node (ref "C6") (pin "2") (pinfunction "2_2") (pintype "passive"))
      (node (ref "C7") (pin "2") (pinfunction "2_2") (pintype "passive"))
      (node (ref "C8") (pin "2") (pinfunction "2_2") (pintype "passive"))
      (node (ref "D23") (pin "A") (pinfunction "A_A") (pintype "passive"))
      (node (ref "D32") (pin "A") (pinfunction "A_A") (pintype "passive"))
      (node (ref "D41") (pin "A") (pinfunction "A_A") (pintype "passive"))
      (node (ref "D50") (pin "A") (pinfunction "A_A") (pintype "passive"))
      (node (ref "D60") (pin "K") (pinfunction "C_K") (pintype "passive"))
      (node (ref "D8") (pin "A") (pinfunction "A_A") (pintype "passive"))
      (node (ref "D9") (pin "K") (pinfunction "C_K") (pintype "passive"))
      (node (ref "IC1") (pin "11") (pinfunction "GND_11") (pintype "power_in"))
      (node (ref "IC1") (pin "31") (pinfunction "GND_31") (pintype "power_in"))
      (node (ref "IC2") (pin "GND") (pinfunction "GND_GND") (pintype "input"))
      (node (ref "IC3") (pin "IN") (pinfunction "IN_IN") (pintype "input"))
      (node (ref "IC4") (pin "GND") (pinfunction "GND_GND") (pintype "input"))
      (node (ref "J1") (pin "1") (pinfunction "1_1") (pintype "passive"))
      (node (ref "J1") (pin "10") (pinfunction "10_10") (pintype "passive"))
      (node (ref "J1") (pin "16") (pinfunction "16_16") (pintype "passive"))
      (node (ref "J1") (pin "5") (pinfunction "5_5") (pintype "passive"))
      (node (ref "J1") (pin "7") (pinfunction "7_7") (pintype "passive"))
      (node (ref "J1") (pin "8") (pinfunction "8_8") (pintype "passive"))
      (node (ref "J1") (pin "9") (pinfunction "9_9") (pintype "passive"))
      (node (ref "OK1") (pin "3") (pinfunction "EMIT_3") (pintype "passive"))
      (node (ref "OK3") (pin "3") (pinfunction "EMIT_3") (pintype "passive"))
      (node (ref "OK4") (pin "3") (pinfunction "EMIT_3") (pintype "passive"))
      (node (ref "OK5") (pin "3") (pinfunction "EMIT_3") (pintype "passive"))
      (node (ref "OK6") (pin "3") (pinfunction "EMIT_3") (pintype "passive"))
      (node (ref "OK7") (pin "3") (pinfunction "EMIT_3") (pintype "passive"))
      (node (ref "R13") (pin "1") (pinfunction "1_1") (pintype "passive"))
      (node (ref "R14") (pin "1") (pinfunction "1_1") (pintype "passive"))
      (node (ref "R24") (pin "1") (pinfunction "1_1") (pintype "passive"))
      (node (ref "R29") (pin "1") (pinfunction "1_1") (pintype "passive"))
      (node (ref "R34") (pin "1") (pinfunction "1_1") (pintype "passive"))
      (node (ref "R39") (pin "1") (pinfunction "1_1") (pintype "passive"))
      (node (ref "R5") (pin "2") (pinfunction "2_2") (pintype "passive"))
      (node (ref "SJR1") (pin "9") (pinfunction "GND_9") (pintype "bidirectional"))
      (node (ref "T1") (pin "E") (pinfunction "E_E") (pintype "passive"))
      (node (ref "T3") (pin "E") (pinfunction "E_E") (pintype "passive"))
      (node (ref "T4") (pin "E") (pinfunction "E_E") (pintype "passive"))
      (node (ref "T5") (pin "E") (pinfunction "E_E") (pintype "passive"))
      (node (ref "T6") (pin "E") (pinfunction "E_E") (pintype "passive"))
      (node (ref "U1") (pin "1") (pinfunction "GND_1") (pintype "bidirectional"))
      (node (ref "V1") (pin "13") (pinfunction "~{G}_13") (pintype "input"))
      (node (ref "V1") (pin "8") (pinfunction "-UB_8") (pintype "power_in"))
      (node (ref "X10") (pin "2") (pinfunction "KL_2") (pintype "passive"))
      (node (ref "X11") (pin "2") (pinfunction "KL_2") (pintype "passive"))
      (node (ref "X14") (pin "2") (pinfunction "KL_2") (pintype "passive"))
      (node (ref "X7") (pin "2") (pinfunction "KL_2") (pintype "passive"))
      (node (ref "X9") (pin "2") (pinfunction "KL_2") (pintype "passive"))
    )
    (net (code "35") (name "HEATER_FED_SIG") (class "Default")
      (node (ref "IC1") (pin "36") (pinfunction "(ADC4)PA4_36") (pintype "bidirectional"))
    )
    (net (code "36") (name "IO0") (class "Default")
      (node (ref "R6") (pin "1") (pinfunction "1_1") (pintype "passive"))
      (node (ref "SJR1") (pin "12") (pinfunction "GPIO0_12") (pintype "bidirectional"))
    )
    (net (code "37") (name "IO2") (class "Default")
      (node (ref "SJR1") (pin "11") (pinfunction "GPIO2_11") (pintype "bidirectional"))
    )
    (net (code "38") (name "L") (class "Default")
      (node (ref "D1") (pin "C") (pinfunction "C_C") (pintype "passive"))
      (node (ref "D13") (pin "C") (pinfunction "C_C") (pintype "passive"))
      (node (ref "D14") (pin "A") (pinfunction "A_A") (pintype "passive"))
      (node (ref "D25") (pin "C") (pinfunction "C_C") (pintype "passive"))
      (node (ref "D30") (pin "A") (pinfunction "A_A") (pintype "passive"))
      (node (ref "D34") (pin "C") (pinfunction "C_C") (pintype "passive"))
      (node (ref "D39") (pin "A") (pinfunction "A_A") (pintype "passive"))
      (node (ref "D43") (pin "C") (pinfunction "C_C") (pintype "passive"))
      (node (ref "D48") (pin "A") (pinfunction "A_A") (pintype "passive"))
      (node (ref "D6") (pin "A") (pinfunction "A_A") (pintype "passive"))
      (node (ref "R1") (pin "2") (pinfunction "2_2") (pintype "passive"))
      (node (ref "R20") (pin "2") (pinfunction "2_2") (pintype "passive"))
      (node (ref "R25") (pin "2") (pinfunction "2_2") (pintype "passive"))
      (node (ref "R30") (pin "2") (pinfunction "2_2") (pintype "passive"))
      (node (ref "R35") (pin "2") (pinfunction "2_2") (pintype "passive"))
      (node (ref "X1") (pin "2") (pinfunction "KL_2") (pintype "passive"))
    )
    (net (code "39") (name "LCD_CLK") (class "Default")
      (node (ref "IC1") (pin "25") (pinfunction "(TMS)PC3_25") (pintype "bidirectional"))
      (node (ref "V1") (pin "11") (pinfunction "SRCK_11") (pintype "input"))
    )
    (net (code "40") (name "LCD_D") (class "Default")
      (node (ref "IC1") (pin "20") (pinfunction "(ICP)PD6_20") (pintype "bidirectional"))
      (node (ref "V1") (pin "14") (pinfunction "SER_14") (pintype "input"))
    )
    (net (code "41") (name "LCD_L") (class "Default")
      (node (ref "IC1") (pin "17") (pinfunction "(INT1)PD3_17") (pintype "bidirectional"))
      (node (ref "V1") (pin "12") (pinfunction "RCK_12") (pintype "input"))
    )
    (net (code "42") (name "LED_PWM") (class "Default")
      (node (ref "IC1") (pin "18") (pinfunction "(OC1B)PD4_18") (pintype "bidirectional"))
      (node (ref "R10") (pin "2") (pinfunction "2_2") (pintype "passive"))
    )
    (net (code "43") (name "N") (class "Default")
      (node (ref "X1") (pin "1") (pinfunction "KL_1") (pintype "passive"))
      (node (ref "X2") (pin "2") (pinfunction "KL_2") (pintype "passive"))
      (node (ref "X3") (pin "2") (pinfunction "KL_2") (pintype "passive"))
      (node (ref "X4") (pin "2") (pinfunction "KL_2") (pintype "passive"))
      (node (ref "X5") (pin "2") (pinfunction "KL_2") (pintype "passive"))
      (node (ref "X6") (pin "2") (pinfunction "KL_2") (pintype "passive"))
    )
    (net (code "44") (name "NRST") (class "Default")
      (node (ref "R3") (pin "2") (pinfunction "2_2") (pintype "passive"))
      (node (ref "SJR1") (pin "1") (pinfunction "REST_1") (pintype "bidirectional"))
    )
    (net (code "45") (name "Net-(B3-Pad+)") (class "Default")
      (node (ref "B3") (pin "+") (pinfunction "+_+") (pintype "passive"))
      (node (ref "R18") (pin "2") (pinfunction "2_2") (pintype "passive"))
    )
    (net (code "46") (name "Net-(C2-Pad1)") (class "Default")
      (node (ref "C2") (pin "1") (pinfunction "1_1") (pintype "passive"))
      (node (ref "D7") (pin "A") (pinfunction "A_A") (pintype "passive"))
      (node (ref "D8") (pin "C") (pinfunction "C_C") (pintype "passive"))
    )
    (net (code "47") (name "Net-(C13-Pad1)") (class "Default")
      (node (ref "C13") (pin "1") (pinfunction "1_1") (pintype "passive"))
      (node (ref "D22") (pin "A") (pinfunction "A_A") (pintype "passive"))
      (node (ref "D23") (pin "C") (pinfunction "C_C") (pintype "passive"))
    )
    (net (code "48") (name "Net-(C15-Pad1)") (class "Default")
      (node (ref "C15") (pin "1") (pinfunction "1_1") (pintype "passive"))
      (node (ref "D31") (pin "A") (pinfunction "A_A") (pintype "passive"))
      (node (ref "D32") (pin "C") (pinfunction "C_C") (pintype "passive"))
    )
    (net (code "49") (name "Net-(C17-Pad1)") (class "Default")
      (node (ref "C17") (pin "1") (pinfunction "1_1") (pintype "passive"))
      (node (ref "D40") (pin "A") (pinfunction "A_A") (pintype "passive"))
      (node (ref "D41") (pin "C") (pinfunction "C_C") (pintype "passive"))
    )
    (net (code "50") (name "Net-(C19-Pad1)") (class "Default")
      (node (ref "C19") (pin "1") (pinfunction "1_1") (pintype "passive"))
      (node (ref "D49") (pin "A") (pinfunction "A_A") (pintype "passive"))
      (node (ref "D50") (pin "C") (pinfunction "C_C") (pintype "passive"))
    )
    (net (code "51") (name "Net-(D1-PadA)") (class "Default")
      (node (ref "D1") (pin "A") (pinfunction "A_A") (pintype "passive"))
      (node (ref "D2") (pin "C") (pinfunction "C_C") (pintype "passive"))
    )
    (net (code "52") (name "Net-(D2-PadA)") (class "Default")
      (node (ref "D2") (pin "A") (pinfunction "A_A") (pintype "passive"))
      (node (ref "D3") (pin "C") (pinfunction "C_C") (pintype "passive"))
    )
    (net (code "53") (name "Net-(D4-PadA)") (class "Default")
      (node (ref "D4") (pin "A") (pinfunction "A_A") (pintype "passive"))
      (node (ref "D5") (pin "C") (pinfunction "C_C") (pintype "passive"))
    )
    (net (code "54") (name "Net-(D5-PadA)") (class "Default")
      (node (ref "D5") (pin "A") (pinfunction "A_A") (pintype "passive"))
      (node (ref "D6") (pin "C") (pinfunction "C_C") (pintype "passive"))
    )
    (net (code "55") (name "Net-(D9-PadA)") (class "Default")
      (node (ref "D9") (pin "A") (pinfunction "A_A") (pintype "passive"))
      (node (ref "R12") (pin "1") (pinfunction "1_1") (pintype "passive"))
    )
    (net (code "56") (name "Net-(D10-C)") (class "Default")
      (node (ref "D10") (pin "K") (pinfunction "C_K") (pintype "passive"))
      (node (ref "K1") (pin "4") (pinfunction "K_4") (pintype "passive"))
      (node (ref "T1") (pin "C") (pinfunction "C_C") (pintype "passive"))
    )
    (net (code "57") (name "Net-(D10-PadA)") (class "Default")
      (node (ref "D10") (pin "A") (pinfunction "A_A") (pintype "passive"))
      (node (ref "R7") (pin "1") (pinfunction "1_1") (pintype "passive"))
    )
    (net (code "58") (name "Net-(D11-PadC)") (class "Default")
      (node (ref "D11") (pin "C") (pinfunction "C_C") (pintype "passive"))
      (node (ref "D12") (pin "A") (pinfunction "A_A") (pintype "passive"))
    )
    (net (code "59") (name "Net-(D12-PadC)") (class "Default")
      (node (ref "D12") (pin "C") (pinfunction "C_C") (pintype "passive"))
      (node (ref "D13") (pin "A") (pinfunction "A_A") (pintype "passive"))
    )
    (net (code "60") (name "Net-(D14-PadC)") (class "Default")
      (node (ref "D14") (pin "C") (pinfunction "C_C") (pintype "passive"))
      (node (ref "D15") (pin "A") (pinfunction "A_A") (pintype "passive"))
    )
    (net (code "61") (name "Net-(D15-PadC)") (class "Default")
      (node (ref "D15") (pin "C") (pinfunction "C_C") (pintype "passive"))
      (node (ref "D52") (pin "A") (pinfunction "A_A") (pintype "passive"))
    )
    (net (code "62") (name "Net-(D24-C)") (class "Default")
      (node (ref "D24") (pin "K") (pinfunction "C_K") (pintype "passive"))
      (node (ref "K2") (pin "4") (pinfunction "K_4") (pintype "passive"))
      (node (ref "T3") (pin "C") (pinfunction "C_C") (pintype "passive"))
    )
    (net (code "63") (name "Net-(D24-PadA)") (class "Default")
      (node (ref "D24") (pin "A") (pinfunction "A_A") (pintype "passive"))
      (node (ref "R22") (pin "1") (pinfunction "1_1") (pintype "passive"))
    )
    (net (code "64") (name "Net-(D25-PadA)") (class "Default")
      (node (ref "D25") (pin "A") (pinfunction "A_A") (pintype "passive"))
      (node (ref "D26") (pin "C") (pinfunction "C_C") (pintype "passive"))
    )
    (net (code "65") (name "Net-(D26-PadA)") (class "Default")
      (node (ref "D26") (pin "A") (pinfunction "A_A") (pintype "passive"))
      (node (ref "D27") (pin "C") (pinfunction "C_C") (pintype "passive"))
    )
    (net (code "66") (name "Net-(D28-PadA)") (class "Default")
      (node (ref "D28") (pin "A") (pinfunction "A_A") (pintype "passive"))
      (node (ref "D29") (pin "C") (pinfunction "C_C") (pintype "passive"))
    )
    (net (code "67") (name "Net-(D29-PadA)") (class "Default")
      (node (ref "D29") (pin "A") (pinfunction "A_A") (pintype "passive"))
      (node (ref "D30") (pin "C") (pinfunction "C_C") (pintype "passive"))
    )
    (net (code "68") (name "Net-(D33-C)") (class "Default")
      (node (ref "D33") (pin "K") (pinfunction "C_K") (pintype "passive"))
      (node (ref "K3") (pin "4") (pinfunction "K_4") (pintype "passive"))
      (node (ref "T4") (pin "C") (pinfunction "C_C") (pintype "passive"))
    )
    (net (code "69") (name "Net-(D33-PadA)") (class "Default")
      (node (ref "D33") (pin "A") (pinfunction "A_A") (pintype "passive"))
      (node (ref "R27") (pin "1") (pinfunction "1_1") (pintype "passive"))
    )
    (net (code "70") (name "Net-(D34-PadA)") (class "Default")
      (node (ref "D34") (pin "A") (pinfunction "A_A") (pintype "passive"))
      (node (ref "D35") (pin "C") (pinfunction "C_C") (pintype "passive"))
    )
    (net (code "71") (name "Net-(D35-PadA)") (class "Default")
      (node (ref "D35") (pin "A") (pinfunction "A_A") (pintype "passive"))
      (node (ref "D36") (pin "C") (pinfunction "C_C") (pintype "passive"))
    )
    (net (code "72") (name "Net-(D37-PadA)") (class "Default")
      (node (ref "D37") (pin "A") (pinfunction "A_A") (pintype "passive"))
      (node (ref "D38") (pin "C") (pinfunction "C_C") (pintype "passive"))
    )
    (net (code "73") (name "Net-(D38-PadA)") (class "Default")
      (node (ref "D38") (pin "A") (pinfunction "A_A") (pintype "passive"))
      (node (ref "D39") (pin "C") (pinfunction "C_C") (pintype "passive"))
    )
    (net (code "74") (name "Net-(D42-C)") (class "Default")
      (node (ref "D42") (pin "K") (pinfunction "C_K") (pintype "passive"))
      (node (ref "K4") (pin "4") (pinfunction "K_4") (pintype "passive"))
      (node (ref "T5") (pin "C") (pinfunction "C_C") (pintype "passive"))
    )
    (net (code "75") (name "Net-(D42-PadA)") (class "Default")
      (node (ref "D42") (pin "A") (pinfunction "A_A") (pintype "passive"))
      (node (ref "R32") (pin "1") (pinfunction "1_1") (pintype "passive"))
    )
    (net (code "76") (name "Net-(D43-PadA)") (class "Default")
      (node (ref "D43") (pin "A") (pinfunction "A_A") (pintype "passive"))
      (node (ref "D44") (pin "C") (pinfunction "C_C") (pintype "passive"))
    )
    (net (code "77") (name "Net-(D44-PadA)") (class "Default")
      (node (ref "D44") (pin "A") (pinfunction "A_A") (pintype "passive"))
      (node (ref "D45") (pin "C") (pinfunction "C_C") (pintype "passive"))
    )
    (net (code "78") (name "Net-(D46-PadA)") (class "Default")
      (node (ref "D46") (pin "A") (pinfunction "A_A") (pintype "passive"))
      (node (ref "D47") (pin "C") (pinfunction "C_C") (pintype "passive"))
    )
    (net (code "79") (name "Net-(D47-PadA)") (class "Default")
      (node (ref "D47") (pin "A") (pinfunction "A_A") (pintype "passive"))
      (node (ref "D48") (pin "C") (pinfunction "C_C") (pintype "passive"))
    )
    (net (code "80") (name "Net-(D51-C)") (class "Default")
      (node (ref "D51") (pin "K") (pinfunction "C_K") (pintype "passive"))
      (node (ref "K5") (pin "4") (pinfunction "K_4") (pintype "passive"))
      (node (ref "T6") (pin "C") (pinfunction "C_C") (pintype "passive"))
    )
    (net (code "81") (name "Net-(D51-PadA)") (class "Default")
      (node (ref "D51") (pin "A") (pinfunction "A_A") (pintype "passive"))
      (node (ref "R37") (pin "1") (pinfunction "1_1") (pintype "passive"))
    )
    (net (code "82") (name "Net-(D60-PadA)") (class "Default")
      (node (ref "D60") (pin "A") (pinfunction "A_A") (pintype "passive"))
      (node (ref "R42") (pin "1") (pinfunction "1_1") (pintype "passive"))
    )
    (net (code "83") (name "Net-(IC1-XTAL1)") (class "Default")
      (node (ref "C5") (pin "2") (pinfunction "2_2") (pintype "passive"))
      (node (ref "IC1") (pin "13") (pinfunction "XTAL1_13") (pintype "bidirectional"))
      (node (ref "Q1") (pin "1") (pinfunction "1_1") (pintype "passive"))
    )
    (net (code "84") (name "Net-(IC1-XTAL2)") (class "Default")
      (node (ref "C3") (pin "2") (pinfunction "2_2") (pintype "passive"))
      (node (ref "IC1") (pin "12") (pinfunction "XTAL2_12") (pintype "bidirectional"))
      (node (ref "Q1") (pin "2") (pinfunction "2_2") (pintype "passive"))
    )
    (net (code "85") (name "Net-(K1-DS2)") (class "Default")
      (node (ref "D3") (pin "A") (pinfunction "A_A") (pintype "passive"))
      (node (ref "D4") (pin "C") (pinfunction "C_C") (pintype "passive"))
      (node (ref "K1") (pin "2") (pinfunction "DS2_2") (pintype "passive"))
      (node (ref "OK1") (pin "2") (pinfunction "C_2") (pintype "passive"))
    )
    (net (code "86") (name "Net-(K2-DS2)") (class "Default")
      (node (ref "D11") (pin "A") (pinfunction "A_A") (pintype "passive"))
      (node (ref "D52") (pin "C") (pinfunction "C_C") (pintype "passive"))
      (node (ref "K2") (pin "2") (pinfunction "DS2_2") (pintype "passive"))
      (node (ref "OK3") (pin "2") (pinfunction "C_2") (pintype "passive"))
    )
    (net (code "87") (name "Net-(K3-DS2)") (class "Default")
      (node (ref "D27") (pin "A") (pinfunction "A_A") (pintype "passive"))
      (node (ref "D28") (pin "C") (pinfunction "C_C") (pintype "passive"))
      (node (ref "K3") (pin "2") (pinfunction "DS2_2") (pintype "passive"))
      (node (ref "OK4") (pin "2") (pinfunction "C_2") (pintype "passive"))
    )
    (net (code "88") (name "Net-(K4-DS2)") (class "Default")
      (node (ref "D36") (pin "A") (pinfunction "A_A") (pintype "passive"))
      (node (ref "D37") (pin "C") (pinfunction "C_C") (pintype "passive"))
      (node (ref "K4") (pin "2") (pinfunction "DS2_2") (pintype "passive"))
      (node (ref "OK5") (pin "2") (pinfunction "C_2") (pintype "passive"))
    )
    (net (code "89") (name "Net-(K5-DS2)") (class "Default")
      (node (ref "D45") (pin "A") (pinfunction "A_A") (pintype "passive"))
      (node (ref "D46") (pin "C") (pinfunction "C_C") (pintype "passive"))
      (node (ref "K5") (pin "2") (pinfunction "DS2_2") (pintype "passive"))
      (node (ref "OK6") (pin "2") (pinfunction "C_2") (pintype "passive"))
    )
    (net (code "90") (name "Net-(OK1-A)") (class "Default")
      (node (ref "OK1") (pin "1") (pinfunction "A_1") (pintype "passive"))
      (node (ref "R1") (pin "1") (pinfunction "1_1") (pintype "passive"))
    )
    (net (code "91") (name "Net-(OK1-COL)") (class "Default")
      (node (ref "C2") (pin "2") (pinfunction "2_2") (pintype "passive"))
      (node (ref "OK1") (pin "4") (pinfunction "COL_4") (pintype "passive"))
      (node (ref "R2") (pin "1") (pinfunction "1_1") (pintype "passive"))
    )
    (net (code "92") (name "Net-(OK3-A)") (class "Default")
      (node (ref "OK3") (pin "1") (pinfunction "A_1") (pintype "passive"))
      (node (ref "R20") (pin "1") (pinfunction "1_1") (pintype "passive"))
    )
    (net (code "93") (name "Net-(OK3-COL)") (class "Default")
      (node (ref "C13") (pin "2") (pinfunction "2_2") (pintype "passive"))
      (node (ref "OK3") (pin "4") (pinfunction "COL_4") (pintype "passive"))
      (node (ref "R21") (pin "1") (pinfunction "1_1") (pintype "passive"))
    )
    (net (code "94") (name "Net-(OK4-A)") (class "Default")
      (node (ref "OK4") (pin "1") (pinfunction "A_1") (pintype "passive"))
      (node (ref "R25") (pin "1") (pinfunction "1_1") (pintype "passive"))
    )
    (net (code "95") (name "Net-(OK4-COL)") (class "Default")
      (node (ref "C15") (pin "2") (pinfunction "2_2") (pintype "passive"))
      (node (ref "OK4") (pin "4") (pinfunction "COL_4") (pintype "passive"))
      (node (ref "R26") (pin "1") (pinfunction "1_1") (pintype "passive"))
    )
    (net (code "96") (name "Net-(OK5-A)") (class "Default")
      (node (ref "OK5") (pin "1") (pinfunction "A_1") (pintype "passive"))
      (node (ref "R30") (pin "1") (pinfunction "1_1") (pintype "passive"))
    )
    (net (code "97") (name "Net-(OK5-COL)") (class "Default")
      (node (ref "C17") (pin "2") (pinfunction "2_2") (pintype "passive"))
      (node (ref "OK5") (pin "4") (pinfunction "COL_4") (pintype "passive"))
      (node (ref "R31") (pin "1") (pinfunction "1_1") (pintype "passive"))
    )
    (net (code "98") (name "Net-(OK6-A)") (class "Default")
      (node (ref "OK6") (pin "1") (pinfunction "A_1") (pintype "passive"))
      (node (ref "R35") (pin "1") (pinfunction "1_1") (pintype "passive"))
    )
    (net (code "99") (name "Net-(OK6-COL)") (class "Default")
      (node (ref "C19") (pin "2") (pinfunction "2_2") (pintype "passive"))
      (node (ref "OK6") (pin "4") (pinfunction "COL_4") (pintype "passive"))
      (node (ref "R36") (pin "1") (pinfunction "1_1") (pintype "passive"))
    )
    (net (code "100") (name "Net-(OK7-A)") (class "Default")
      (node (ref "OK7") (pin "1") (pinfunction "A_1") (pintype "passive"))
      (node (ref "R18") (pin "1") (pinfunction "1_1") (pintype "passive"))
    )
    (net (code "101") (name "Net-(OK7-C)") (class "Default")
      (node (ref "B3") (pin "-") (pinfunction "-_-") (pintype "passive"))
      (node (ref "OK7") (pin "2") (pinfunction "C_2") (pintype "passive"))
    )
    (net (code "102") (name "Net-(R9-Pad2)") (class "Default")
      (node (ref "R9") (pin "2") (pinfunction "2_2") (pintype "passive"))
      (node (ref "T1") (pin "B") (pinfunction "B_B") (pintype "passive"))
    )
    (net (code "103") (name "Net-(R14-Pad2)") (class "Default")
      (node (ref "R14") (pin "2") (pinfunction "2_2") (pintype "passive"))
      (node (ref "SG1") (pin "-") (pinfunction "-_-") (pintype "passive"))
    )
    (net (code "104") (name "Net-(R23-Pad2)") (class "Default")
      (node (ref "R23") (pin "2") (pinfunction "2_2") (pintype "passive"))
      (node (ref "T3") (pin "B") (pinfunction "B_B") (pintype "passive"))
    )
    (net (code "105") (name "Net-(R28-Pad2)") (class "Default")
      (node (ref "R28") (pin "2") (pinfunction "2_2") (pintype "passive"))
      (node (ref "T4") (pin "B") (pinfunction "B_B") (pintype "passive"))
    )
    (net (code "106") (name "Net-(R33-Pad2)") (class "Default")
      (node (ref "R33") (pin "2") (pinfunction "2_2") (pintype "passive"))
      (node (ref "T5") (pin "B") (pinfunction "B_B") (pintype "passive"))
    )
    (net (code "107") (name "Net-(R38-Pad2)") (class "Default")
      (node (ref "R38") (pin "2") (pinfunction "2_2") (pintype "passive"))
      (node (ref "T6") (pin "B") (pinfunction "B_B") (pintype "passive"))
    )
    (net (code "108") (name "OK") (class "Default")
      (node (ref "IC1") (pin "39") (pinfunction "(ADC1)PA1_39") (pintype "bidirectional"))
      (node (ref "X13") (pin "2") (pinfunction "KL_2") (pintype "passive"))
    )
    (net (code "109") (name "OUT_PUMP") (class "Default")
      (node (ref "K5") (pin "1") (pinfunction "DS1_1") (pintype "passive"))
      (node (ref "X6") (pin "1") (pinfunction "KL_1") (pintype "passive"))
    )
    (net (code "110") (name "OUT_S1_GAS") (class "Default")
      (node (ref "K4") (pin "1") (pinfunction "DS1_1") (pintype "passive"))
      (node (ref "X2") (pin "1") (pinfunction "KL_1") (pintype "passive"))
    )
    (net (code "111") (name "OUT_S2_WAT") (class "Default")
      (node (ref "K3") (pin "1") (pinfunction "DS1_1") (pintype "passive"))
      (node (ref "X3") (pin "1") (pinfunction "KL_1") (pintype "passive"))
    )
    (net (code "112") (name "OUT_S3_VAP") (class "Default")
      (node (ref "K2") (pin "1") (pinfunction "DS1_1") (pintype "passive"))
      (node (ref "X4") (pin "1") (pinfunction "KL_1") (pintype "passive"))
    )
    (net (code "113") (name "OUT_S4_DRY") (class "Default")
      (node (ref "K1") (pin "1") (pinfunction "DS1_1") (pintype "passive"))
      (node (ref "X5") (pin "1") (pinfunction "KL_1") (pintype "passive"))
    )
    (net (code "114") (name "PRES_SEN") (class "Default")
      (node (ref "IC1") (pin "6") (pinfunction "(MOSI)PB5_6") (pintype "bidirectional"))
      (node (ref "X10") (pin "1") (pinfunction "KL_1") (pintype "passive"))
    )
    (net (code "115") (name "PUMP_FED_SIG") (class "Default")
      (node (ref "C33") (pin "1") (pinfunction "1_1") (pintype "passive"))
      (node (ref "D22") (pin "C") (pinfunction "C_C") (pintype "passive"))
      (node (ref "IC1") (pin "23") (pinfunction "(SDA)PC1_23") (pintype "bidirectional"))
      (node (ref "R24") (pin "2") (pinfunction "2_2") (pintype "passive"))
    )
    (net (code "116") (name "REST") (class "Default")
      (node (ref "IC1") (pin "9") (pinfunction "RESET_9") (pintype "input"))
      (node (ref "JP1") (pin "2") (pinfunction "2_2") (pintype "passive"))
      (node (ref "R8") (pin "1") (pinfunction "1_1") (pintype "passive"))
    )
    (net (code "117") (name "REST_OUT") (class "Default")
      (node (ref "JP1") (pin "1") (pinfunction "1_1") (pintype "passive"))
      (node (ref "SJR1") (pin "13") (pinfunction "GPIO4_13") (pintype "bidirectional"))
    )
    (net (code "118") (name "RS") (class "Default")
      (node (ref "J1") (pin "4") (pinfunction "4_4") (pintype "passive"))
      (node (ref "V1") (pin "7") (pinfunction "QH_7") (pintype "tri_state"))
    )
    (net (code "119") (name "S1_GAS_FED_SIG") (class "Default")
      (node (ref "C35") (pin "1") (pinfunction "1_1") (pintype "passive"))
      (node (ref "D40") (pin "C") (pinfunction "C_C") (pintype "passive"))
      (node (ref "IC1") (pin "35") (pinfunction "(ADC5)PA5_35") (pintype "bidirectional"))
      (node (ref "R34") (pin "2") (pinfunction "2_2") (pintype "passive"))
    )
    (net (code "120") (name "S2_WAT_FED_SIG") (class "Default")
      (node (ref "C34") (pin "1") (pinfunction "1_1") (pintype "passive"))
      (node (ref "D31") (pin "C") (pinfunction "C_C") (pintype "passive"))
      (node (ref "IC1") (pin "27") (pinfunction "(TDI)PC5_27") (pintype "bidirectional"))
      (node (ref "R29") (pin "2") (pinfunction "2_2") (pintype "passive"))
    )
    (net (code "121") (name "S3_VAP_FED_SIG") (class "Default")
      (node (ref "C36") (pin "1") (pinfunction "1_1") (pintype "passive"))
      (node (ref "D49") (pin "C") (pinfunction "C_C") (pintype "passive"))
      (node (ref "IC1") (pin "29") (pinfunction "(TOSC2)PC7_29") (pintype "bidirectional"))
      (node (ref "R39") (pin "2") (pinfunction "2_2") (pintype "passive"))
    )
    (net (code "122") (name "S4_DRY_FED_SIG") (class "Default")
      (node (ref "C32") (pin "1") (pinfunction "1_1") (pintype "passive"))
      (node (ref "D7") (pin "C") (pinfunction "C_C") (pintype "passive"))
      (node (ref "IC1") (pin "21") (pinfunction "(OC2)PD7_21") (pintype "bidirectional"))
      (node (ref "R13") (pin "2") (pinfunction "2_2") (pintype "passive"))
    )
    (net (code "123") (name "SCL3") (class "Default")
      (node (ref "SJR1") (pin "14") (pinfunction "GPIO5_14") (pintype "bidirectional"))
    )
    (net (code "124") (name "TCK+") (class "Default")
      (node (ref "U1") (pin "3") (pinfunction "T+_3") (pintype "bidirectional"))
      (node (ref "X15") (pin "2") (pinfunction "KL_2") (pintype "passive"))
    )
    (net (code "125") (name "TCK-") (class "Default")
      (node (ref "U1") (pin "2") (pinfunction "T-_2") (pintype "bidirectional"))
      (node (ref "X15") (pin "1") (pinfunction "KL_1") (pintype "passive"))
    )
    (net (code "126") (name "T_CLK") (class "Default")
      (node (ref "IC1") (pin "3") (pinfunction "(AIN0/INT2)PB2_3") (pintype "bidirectional"))
      (node (ref "U1") (pin "6") (pinfunction "~{CS}_6") (pintype "bidirectional"))
    )
    (net (code "127") (name "T_CS") (class "Default")
      (node (ref "IC1") (pin "2") (pinfunction "(T1)PB1_2") (pintype "bidirectional"))
      (node (ref "U1") (pin "5") (pinfunction "SCK_5") (pintype "bidirectional"))
    )
    (net (code "128") (name "T_DO") (class "Default")
      (node (ref "IC1") (pin "4") (pinfunction "(AIN1/OC0)PB3_4") (pintype "bidirectional"))
      (node (ref "U1") (pin "7") (pinfunction "(MI)SO_7") (pintype "bidirectional"))
    )
    (net (code "129") (name "UP") (class "Default")
      (node (ref "IC1") (pin "38") (pinfunction "(ADC2)PA2_38") (pintype "bidirectional"))
      (node (ref "X13") (pin "1") (pinfunction "KL_1") (pintype "passive"))
    )
    (net (code "130") (name "VEE") (class "Default")
      (node (ref "C11") (pin "2") (pinfunction "2_2") (pintype "passive"))
      (node (ref "C4") (pin "+") (pinfunction "+_+") (pintype "passive"))
      (node (ref "J1") (pin "3") (pinfunction "3_3") (pintype "passive"))
      (node (ref "R11") (pin "1") (pinfunction "1_1") (pintype "passive"))
    )
    (net (code "131") (name "VIN") (class "Default")
      (node (ref "B2") (pin "+") (pinfunction "+_+") (pintype "passive"))
      (node (ref "C22") (pin "+") (pinfunction "+_+") (pintype "passive"))
      (node (ref "C23") (pin "2") (pinfunction "2_2") (pintype "passive"))
      (node (ref "IC2") (pin "IN") (pinfunction "IN_IN") (pintype "input"))
      (node (ref "IC4") (pin "IN") (pinfunction "IN_IN") (pintype "input"))
      (node (ref "R42") (pin "2") (pinfunction "2_2") (pintype "passive"))
    )
    (net (code "132") (name "WATER_SEN") (class "Default")
      (node (ref "IC1") (pin "34") (pinfunction "(ADC6)PA6_34") (pintype "bidirectional"))
      (node (ref "R16") (pin "1") (pinfunction "1_1") (pintype "passive"))
      (node (ref "X9") (pin "1") (pinfunction "KL_1") (pintype "passive"))
    )
    (net (code "133") (name "ZERO_CROSS") (class "Default")
      (node (ref "IC1") (pin "16") (pinfunction "(INT0)PD2_16") (pintype "bidirectional"))
      (node (ref "OK7") (pin "4") (pinfunction "COL_4") (pintype "passive"))
      (node (ref "R19") (pin "2") (pinfunction "2_2") (pintype "passive"))
    )
    (net (code "134") (name "unconnected-(IC1-(SS)PB4-Pad5)") (class "Default")
      (node (ref "IC1") (pin "5") (pinfunction "(SS)PB4_5") (pintype "bidirectional"))
    )
    (net (code "135") (name "unconnected-(IC1-AREF-Pad32)") (class "Default")
      (node (ref "IC1") (pin "32") (pinfunction "AREF_32") (pintype "passive"))
    )
    (net (code "136") (name "unconnected-(SJR1-CS0-Pad17)") (class "Default")
      (node (ref "SJR1") (pin "17") (pinfunction "CS0_17") (pintype "bidirectional"))
    )
    (net (code "137") (name "unconnected-(SJR1-GPIO9-Pad19)") (class "Default")
      (node (ref "SJR1") (pin "19") (pinfunction "GPIO9_19") (pintype "bidirectional"))
    )
    (net (code "138") (name "unconnected-(SJR1-GPIO10-Pad20)") (class "Default")
      (node (ref "SJR1") (pin "20") (pinfunction "GPIO10_20") (pintype "bidirectional"))
    )
    (net (code "139") (name "unconnected-(SJR1-MISO-Pad18)") (class "Default")
      (node (ref "SJR1") (pin "18") (pinfunction "MISO_18") (pintype "bidirectional"))
    )
    (net (code "140") (name "unconnected-(SJR1-MOSI-Pad21)") (class "Default")
      (node (ref "SJR1") (pin "21") (pinfunction "MOSI_21") (pintype "bidirectional"))
    )
    (net (code "141") (name "unconnected-(SJR1-SCLK-Pad22)") (class "Default")
      (node (ref "SJR1") (pin "22") (pinfunction "SCLK_22") (pintype "bidirectional"))
    )
    (net (code "142") (name "unconnected-(V1C-QE-Pad4)") (class "Default")
      (node (ref "V1") (pin "4") (pinfunction "QE_4") (pintype "tri_state"))
    )
    (net (code "143") (name "unconnected-(V1C-QF-Pad5)") (class "Default")
      (node (ref "V1") (pin "5") (pinfunction "QF_5") (pintype "tri_state"))
    )
    (net (code "144") (name "unconnected-(V1C-QH*-Pad9)") (class "Default")
      (node (ref "V1") (pin "9") (pinfunction "QH*_9") (pintype "output"))
    )
  )
)
